# ZYNQ.net
KiCad netlist of a schematic drawn in Altium Designer
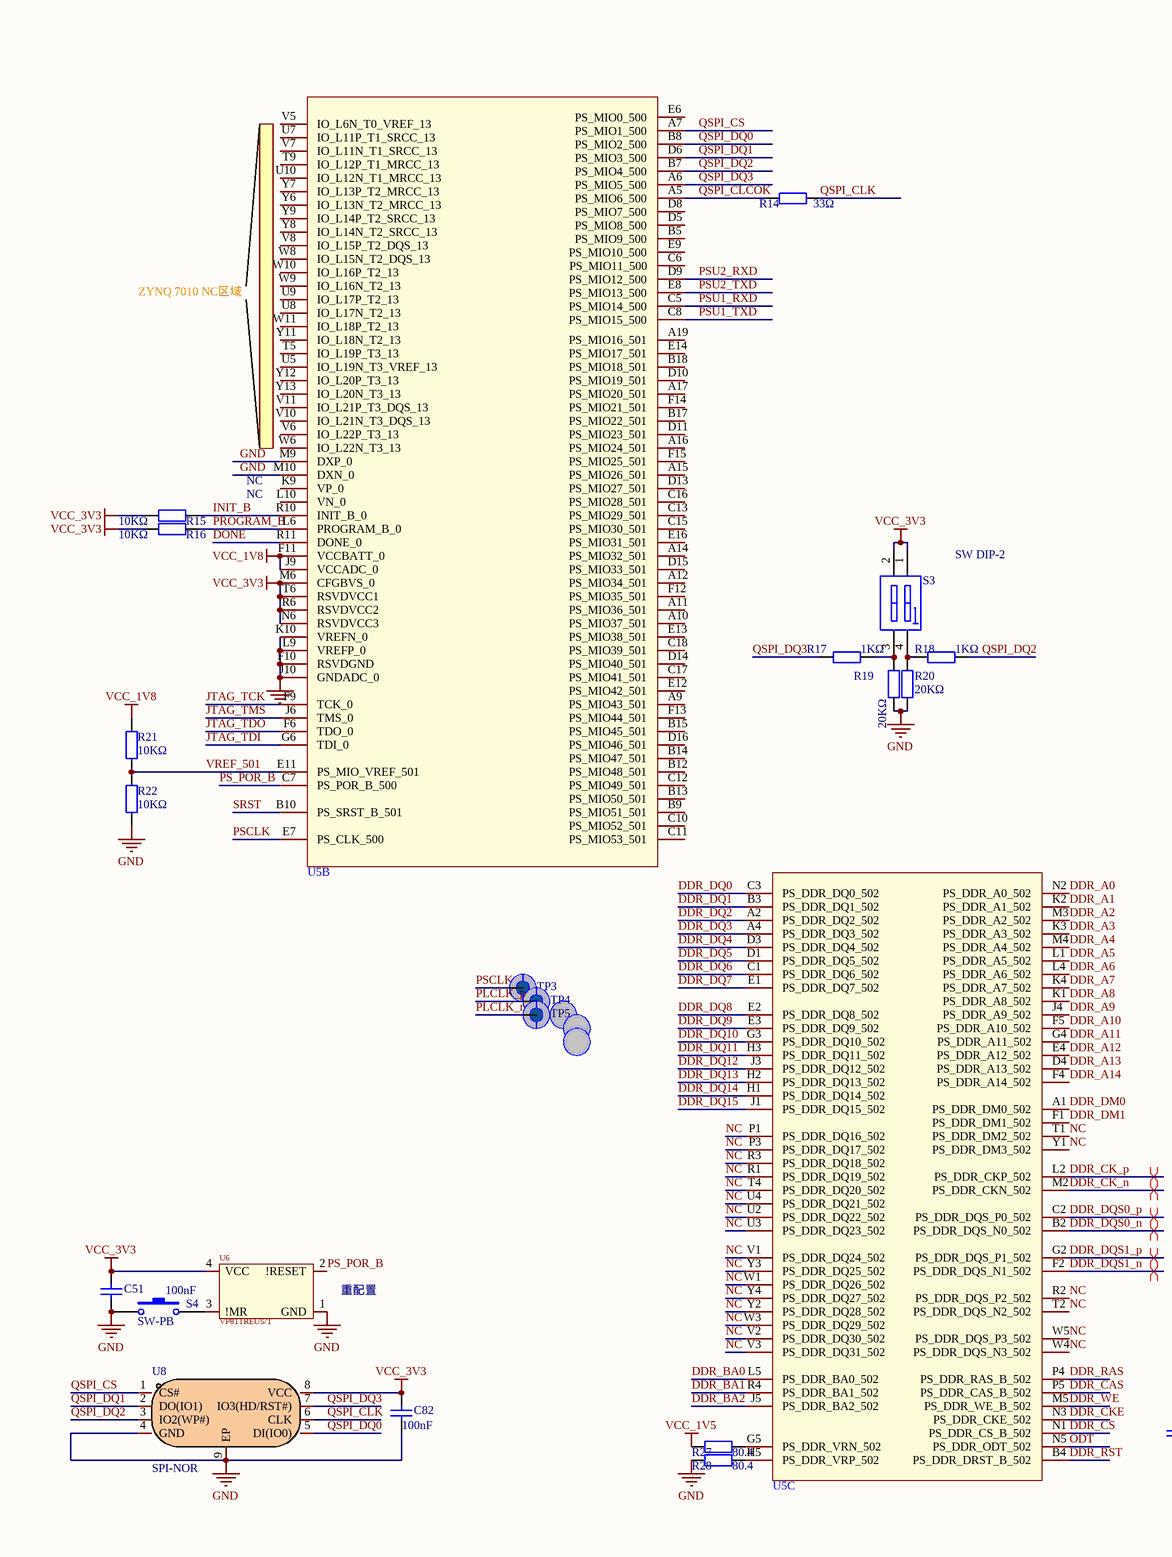
[diagram p0: ZYNQ.SchDoc, left]
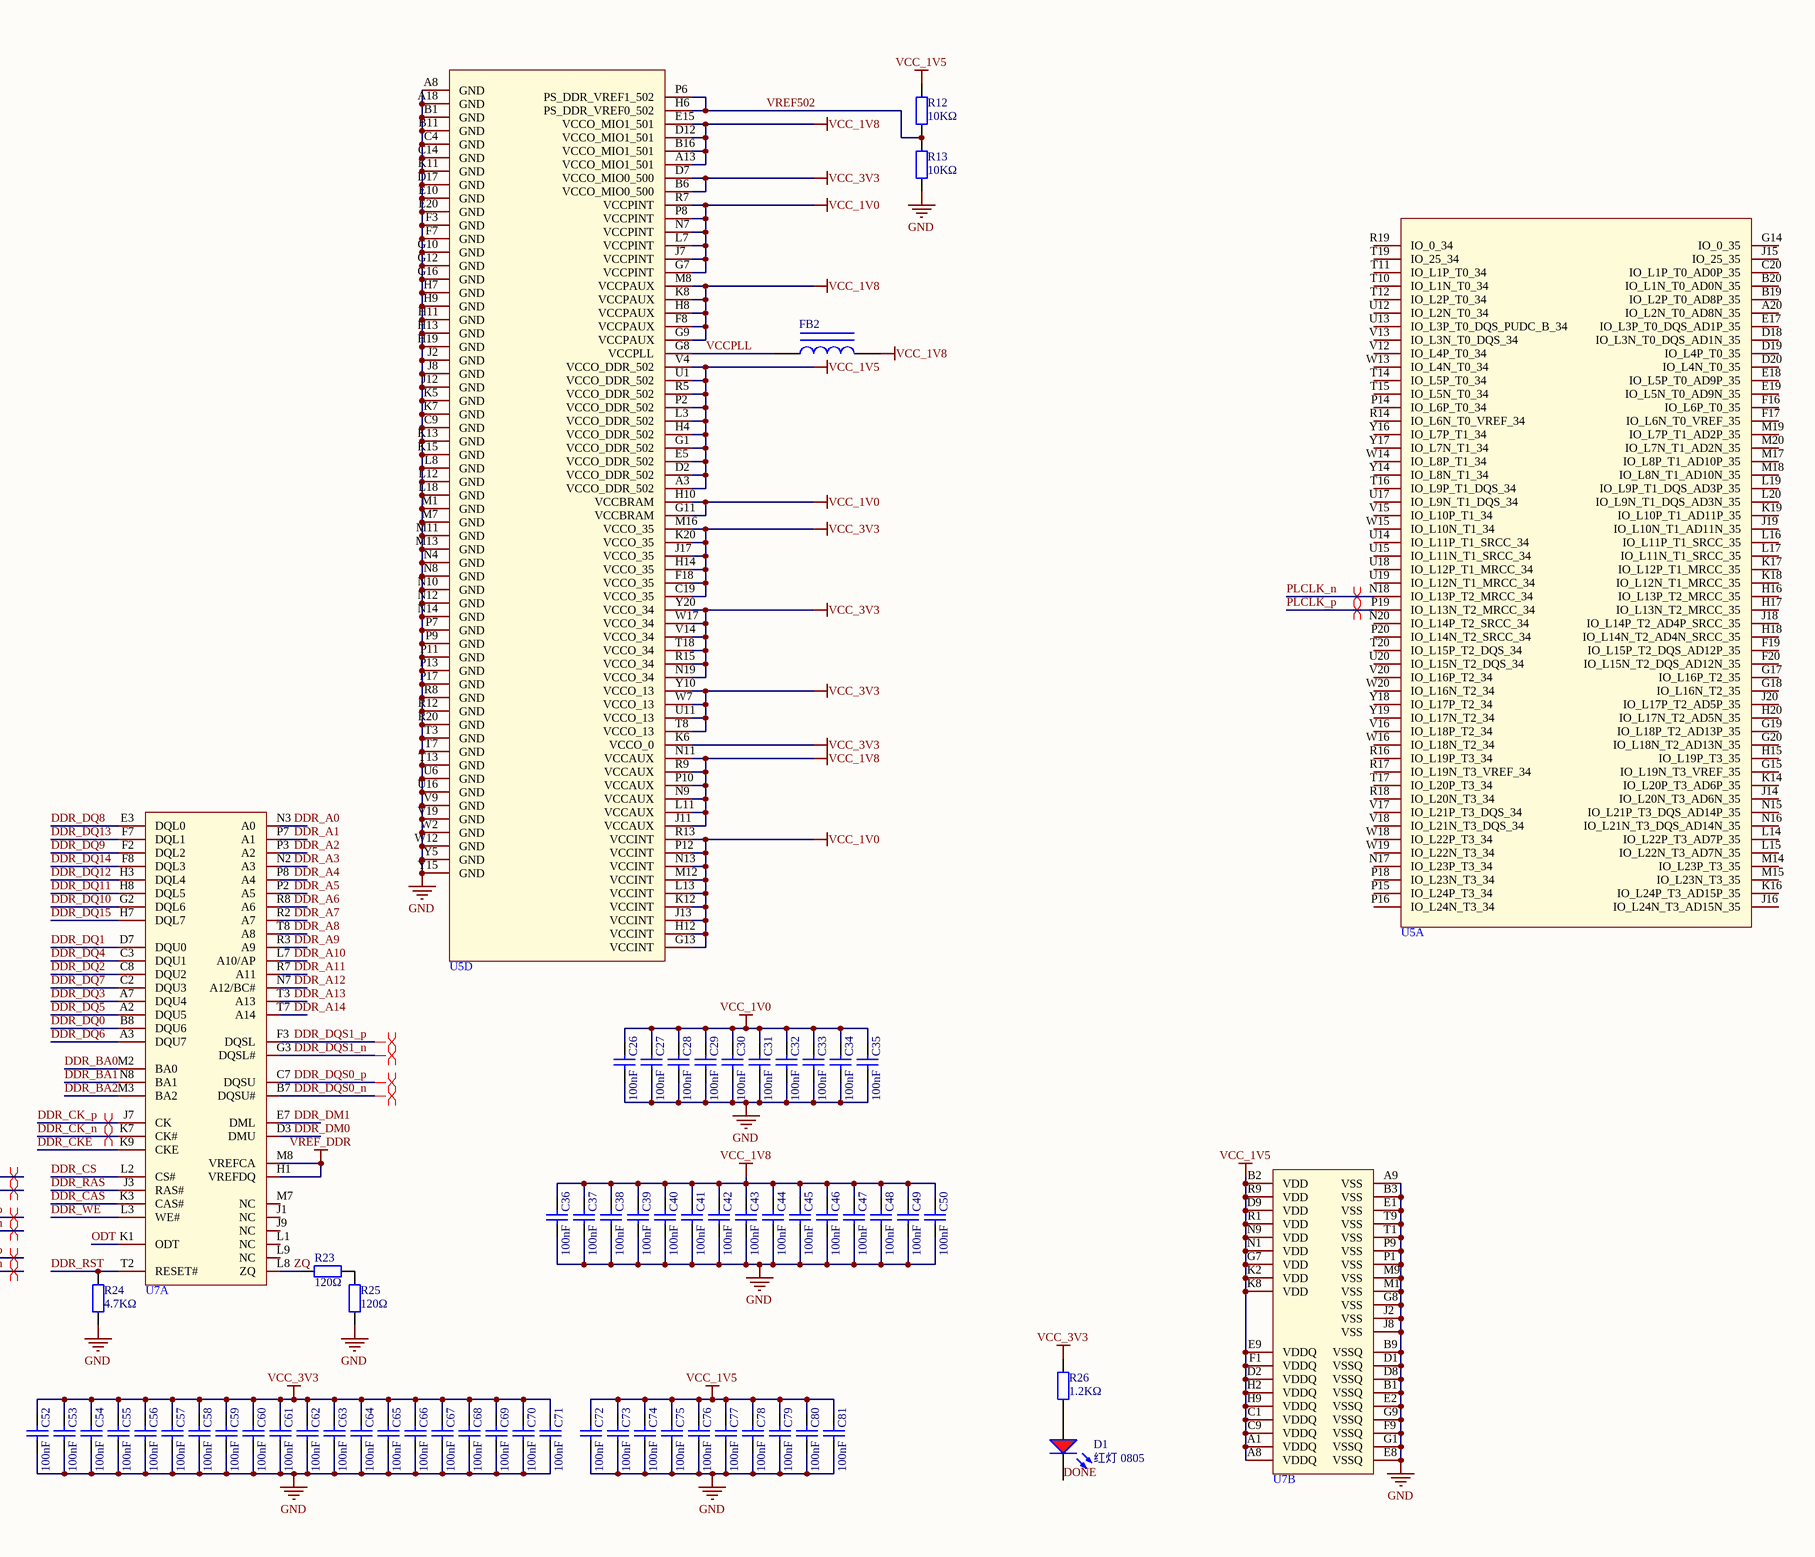
[diagram p1: ZYNQ.SchDoc, right]

(export (version "E")
  (design (tool "Eeschema 10.0.6"))
  (components
    (comp (ref "C26")
      (value "100nF")
      (footprint "0201")
      (description "贴片电容")
      (libsource (lib "Miscellaneous Devices LC") (part "0402 100nF (104) 10% 16V"))
    )
    (comp (ref "C27")
      (value "100nF")
      (footprint "0201")
      (description "贴片电容")
      (libsource (lib "Miscellaneous Devices LC") (part "0402 100nF (104) 10% 16V"))
    )
    (comp (ref "C28")
      (value "100nF")
      (footprint "0201")
      (description "贴片电容")
      (libsource (lib "Miscellaneous Devices LC") (part "0402 100nF (104) 10% 16V"))
    )
    (comp (ref "C29")
      (value "100nF")
      (footprint "0201")
      (description "贴片电容")
      (libsource (lib "Miscellaneous Devices LC") (part "0402 100nF (104) 10% 16V"))
    )
    (comp (ref "C30")
      (value "100nF")
      (footprint "0201")
      (description "贴片电容")
      (libsource (lib "Miscellaneous Devices LC") (part "0402 100nF (104) 10% 16V"))
    )
    (comp (ref "C31")
      (value "100nF")
      (footprint "0201")
      (description "贴片电容")
      (libsource (lib "Miscellaneous Devices LC") (part "0402 100nF (104) 10% 16V"))
    )
    (comp (ref "C32")
      (value "100nF")
      (footprint "0201")
      (description "贴片电容")
      (libsource (lib "Miscellaneous Devices LC") (part "0402 100nF (104) 10% 16V"))
    )
    (comp (ref "C33")
      (value "100nF")
      (footprint "0201")
      (description "贴片电容")
      (libsource (lib "Miscellaneous Devices LC") (part "0402 100nF (104) 10% 16V"))
    )
    (comp (ref "C34")
      (value "100nF")
      (footprint "0201")
      (description "贴片电容")
      (libsource (lib "Miscellaneous Devices LC") (part "0402 100nF (104) 10% 16V"))
    )
    (comp (ref "C35")
      (value "100nF")
      (footprint "0201")
      (description "贴片电容")
      (libsource (lib "Miscellaneous Devices LC") (part "0402 100nF (104) 10% 16V"))
    )
    (comp (ref "C36")
      (value "100nF")
      (footprint "0201")
      (description "贴片电容")
      (libsource (lib "Miscellaneous Devices LC") (part "0402 100nF (104) 10% 16V"))
    )
    (comp (ref "C37")
      (value "100nF")
      (footprint "0201")
      (description "贴片电容")
      (libsource (lib "Miscellaneous Devices LC") (part "0402 100nF (104) 10% 16V"))
    )
    (comp (ref "C38")
      (value "100nF")
      (footprint "0201")
      (description "贴片电容")
      (libsource (lib "Miscellaneous Devices LC") (part "0402 100nF (104) 10% 16V"))
    )
    (comp (ref "C39")
      (value "100nF")
      (footprint "0201")
      (description "贴片电容")
      (libsource (lib "Miscellaneous Devices LC") (part "0402 100nF (104) 10% 16V"))
    )
    (comp (ref "C40")
      (value "100nF")
      (footprint "0201")
      (description "贴片电容")
      (libsource (lib "Miscellaneous Devices LC") (part "0402 100nF (104) 10% 16V"))
    )
    (comp (ref "C41")
      (value "100nF")
      (footprint "0201")
      (description "贴片电容")
      (libsource (lib "Miscellaneous Devices LC") (part "0402 100nF (104) 10% 16V"))
    )
    (comp (ref "C42")
      (value "100nF")
      (footprint "0201")
      (description "贴片电容")
      (libsource (lib "Miscellaneous Devices LC") (part "0402 100nF (104) 10% 16V"))
    )
    (comp (ref "C43")
      (value "100nF")
      (footprint "0201")
      (description "贴片电容")
      (libsource (lib "Miscellaneous Devices LC") (part "0402 100nF (104) 10% 16V"))
    )
    (comp (ref "C44")
      (value "100nF")
      (footprint "0201")
      (description "贴片电容")
      (libsource (lib "Miscellaneous Devices LC") (part "0402 100nF (104) 10% 16V"))
    )
    (comp (ref "C45")
      (value "100nF")
      (footprint "0201")
      (description "贴片电容")
      (libsource (lib "Miscellaneous Devices LC") (part "0402 100nF (104) 10% 16V"))
    )
    (comp (ref "C46")
      (value "100nF")
      (footprint "0201")
      (description "贴片电容")
      (libsource (lib "Miscellaneous Devices LC") (part "0402 100nF (104) 10% 16V"))
    )
    (comp (ref "C47")
      (value "100nF")
      (footprint "0201")
      (description "贴片电容")
      (libsource (lib "Miscellaneous Devices LC") (part "0402 100nF (104) 10% 16V"))
    )
    (comp (ref "C48")
      (value "100nF")
      (footprint "0201")
      (description "贴片电容")
      (libsource (lib "Miscellaneous Devices LC") (part "0402 100nF (104) 10% 16V"))
    )
    (comp (ref "C49")
      (value "100nF")
      (footprint "0201")
      (description "贴片电容")
      (libsource (lib "Miscellaneous Devices LC") (part "0402 100nF (104) 10% 16V"))
    )
    (comp (ref "C50")
      (value "100nF")
      (footprint "0201")
      (description "贴片电容")
      (libsource (lib "Miscellaneous Devices LC") (part "0402 100nF (104) 10% 16V"))
    )
    (comp (ref "C51")
      (value "100nF")
      (footprint "0805_C")
      (description "贴片电容")
      (libsource (lib "Miscellaneous Devices LC") (part "0402 100nF (104) 10% 16V"))
    )
    (comp (ref "C52")
      (value "100nF")
      (footprint "0201")
      (description "贴片电容")
      (libsource (lib "Miscellaneous Devices LC") (part "0402 100nF (104) 10% 16V"))
    )
    (comp (ref "C53")
      (value "100nF")
      (footprint "0201")
      (description "贴片电容")
      (libsource (lib "Miscellaneous Devices LC") (part "0402 100nF (104) 10% 16V"))
    )
    (comp (ref "C54")
      (value "100nF")
      (footprint "0201")
      (description "贴片电容")
      (libsource (lib "Miscellaneous Devices LC") (part "0402 100nF (104) 10% 16V"))
    )
    (comp (ref "C55")
      (value "100nF")
      (footprint "0201")
      (description "贴片电容")
      (libsource (lib "Miscellaneous Devices LC") (part "0402 100nF (104) 10% 16V"))
    )
    (comp (ref "C56")
      (value "100nF")
      (footprint "0201")
      (description "贴片电容")
      (libsource (lib "Miscellaneous Devices LC") (part "0402 100nF (104) 10% 16V"))
    )
    (comp (ref "C57")
      (value "100nF")
      (footprint "0201")
      (description "贴片电容")
      (libsource (lib "Miscellaneous Devices LC") (part "0402 100nF (104) 10% 16V"))
    )
    (comp (ref "C58")
      (value "100nF")
      (footprint "0201")
      (description "贴片电容")
      (libsource (lib "Miscellaneous Devices LC") (part "0402 100nF (104) 10% 16V"))
    )
    (comp (ref "C59")
      (value "100nF")
      (footprint "0201")
      (description "贴片电容")
      (libsource (lib "Miscellaneous Devices LC") (part "0402 100nF (104) 10% 16V"))
    )
    (comp (ref "C60")
      (value "100nF")
      (footprint "0201")
      (description "贴片电容")
      (libsource (lib "Miscellaneous Devices LC") (part "0402 100nF (104) 10% 16V"))
    )
    (comp (ref "C61")
      (value "100nF")
      (footprint "0201")
      (description "贴片电容")
      (libsource (lib "Miscellaneous Devices LC") (part "0402 100nF (104) 10% 16V"))
    )
    (comp (ref "C62")
      (value "100nF")
      (footprint "0201")
      (description "贴片电容")
      (libsource (lib "Miscellaneous Devices LC") (part "0402 100nF (104) 10% 16V"))
    )
    (comp (ref "C63")
      (value "100nF")
      (footprint "0201")
      (description "贴片电容")
      (libsource (lib "Miscellaneous Devices LC") (part "0402 100nF (104) 10% 16V"))
    )
    (comp (ref "C64")
      (value "100nF")
      (footprint "0201")
      (description "贴片电容")
      (libsource (lib "Miscellaneous Devices LC") (part "0402 100nF (104) 10% 16V"))
    )
    (comp (ref "C65")
      (value "100nF")
      (footprint "0201")
      (description "贴片电容")
      (libsource (lib "Miscellaneous Devices LC") (part "0402 100nF (104) 10% 16V"))
    )
    (comp (ref "C66")
      (value "100nF")
      (footprint "0201")
      (description "贴片电容")
      (libsource (lib "Miscellaneous Devices LC") (part "0402 100nF (104) 10% 16V"))
    )
    (comp (ref "C67")
      (value "100nF")
      (footprint "0201")
      (description "贴片电容")
      (libsource (lib "Miscellaneous Devices LC") (part "0402 100nF (104) 10% 16V"))
    )
    (comp (ref "C68")
      (value "100nF")
      (footprint "0201")
      (description "贴片电容")
      (libsource (lib "Miscellaneous Devices LC") (part "0402 100nF (104) 10% 16V"))
    )
    (comp (ref "C69")
      (value "100nF")
      (footprint "0201")
      (description "贴片电容")
      (libsource (lib "Miscellaneous Devices LC") (part "0402 100nF (104) 10% 16V"))
    )
    (comp (ref "C70")
      (value "100nF")
      (footprint "0201")
      (description "贴片电容")
      (libsource (lib "Miscellaneous Devices LC") (part "0402 100nF (104) 10% 16V"))
    )
    (comp (ref "C71")
      (value "100nF")
      (footprint "0201")
      (description "贴片电容")
      (libsource (lib "Miscellaneous Devices LC") (part "0402 100nF (104) 10% 16V"))
    )
    (comp (ref "C72")
      (value "100nF")
      (footprint "0201")
      (description "贴片电容")
      (libsource (lib "Miscellaneous Devices LC") (part "0402 100nF (104) 10% 16V"))
    )
    (comp (ref "C73")
      (value "100nF")
      (footprint "0201")
      (description "贴片电容")
      (libsource (lib "Miscellaneous Devices LC") (part "0402 100nF (104) 10% 16V"))
    )
    (comp (ref "C74")
      (value "100nF")
      (footprint "0201")
      (description "贴片电容")
      (libsource (lib "Miscellaneous Devices LC") (part "0402 100nF (104) 10% 16V"))
    )
    (comp (ref "C75")
      (value "100nF")
      (footprint "0201")
      (description "贴片电容")
      (libsource (lib "Miscellaneous Devices LC") (part "0402 100nF (104) 10% 16V"))
    )
    (comp (ref "C76")
      (value "100nF")
      (footprint "0201")
      (description "贴片电容")
      (libsource (lib "Miscellaneous Devices LC") (part "0402 100nF (104) 10% 16V"))
    )
    (comp (ref "C77")
      (value "100nF")
      (footprint "0201")
      (description "贴片电容")
      (libsource (lib "Miscellaneous Devices LC") (part "0402 100nF (104) 10% 16V"))
    )
    (comp (ref "C78")
      (value "100nF")
      (footprint "0201")
      (description "贴片电容")
      (libsource (lib "Miscellaneous Devices LC") (part "0402 100nF (104) 10% 16V"))
    )
    (comp (ref "C79")
      (value "100nF")
      (footprint "0201")
      (description "贴片电容")
      (libsource (lib "Miscellaneous Devices LC") (part "0402 100nF (104) 10% 16V"))
    )
    (comp (ref "C80")
      (value "100nF")
      (footprint "0201")
      (description "贴片电容")
      (libsource (lib "Miscellaneous Devices LC") (part "0402 100nF (104) 10% 16V"))
    )
    (comp (ref "C81")
      (value "100nF")
      (footprint "0201")
      (description "贴片电容")
      (libsource (lib "Miscellaneous Devices LC") (part "0402 100nF (104) 10% 16V"))
    )
    (comp (ref "C82")
      (value "100nF")
      (footprint "0805_C")
      (description "贴片电容")
      (libsource (lib "Miscellaneous Devices LC") (part "0402 100nF (104) 10% 16V"))
    )
    (comp (ref "D1")
      (value "红灯 0805")
      (footprint "0805_LED_S1")
      (description "发光二极管")
      (libsource (lib "Miscellaneous Devices LC") (part "0805 红灯"))
    )
    (comp (ref "FB2")
      (value "100Ω ±25% 100MHz")
      (footprint "0805_L")
      (description "贴片磁珠")
      (libsource (lib "Miscellaneous Devices LC") (part "0805 100Ω 25% 100MHz"))
    )
    (comp (ref "R12")
      (value "10KΩ")
      (footprint "0201")
      (description "贴片电阻")
      (libsource (lib "Miscellaneous Devices LC") (part "0805 10KΩ (1002) 1%"))
    )
    (comp (ref "R13")
      (value "10KΩ")
      (footprint "0201")
      (description "贴片电阻")
      (libsource (lib "Miscellaneous Devices LC") (part "0805 10KΩ (1002) 1%"))
    )
    (comp (ref "R14")
      (value "33Ω")
      (footprint "0805_R")
      (description "贴片电阻")
      (libsource (lib "Miscellaneous Devices LC") (part "0402 33Ω (33R0) 1%"))
    )
    (comp (ref "R15")
      (value "10KΩ")
      (footprint "0201")
      (description "贴片电阻")
      (libsource (lib "Miscellaneous Devices LC") (part "0402 4.7KΩ (4701) 1%"))
    )
    (comp (ref "R16")
      (value "10KΩ")
      (footprint "0201")
      (description "贴片电阻")
      (libsource (lib "Miscellaneous Devices LC") (part "0402 4.7KΩ (4701) 1%"))
    )
    (comp (ref "R17")
      (value "1KΩ")
      (footprint "0805_R")
      (description "贴片电阻")
      (libsource (lib "Miscellaneous Devices LC") (part "0402 10KΩ (1002) 1%"))
    )
    (comp (ref "R18")
      (value "1KΩ")
      (footprint "0805_R")
      (description "贴片电阻")
      (libsource (lib "Miscellaneous Devices LC") (part "0402 10KΩ (1002) 1%"))
    )
    (comp (ref "R19")
      (value "20KΩ")
      (footprint "0805_R")
      (description "贴片电阻")
      (libsource (lib "Miscellaneous Devices LC") (part "0402 20KΩ (2002) 1%"))
    )
    (comp (ref "R20")
      (value "20KΩ")
      (footprint "0805_R")
      (description "贴片电阻")
      (libsource (lib "Miscellaneous Devices LC") (part "0402 20KΩ (2002) 1%"))
    )
    (comp (ref "R21")
      (value "10KΩ")
      (footprint "0201")
      (description "贴片电阻")
      (libsource (lib "Miscellaneous Devices LC") (part "0805 10KΩ (1002) 1%"))
    )
    (comp (ref "R22")
      (value "10KΩ")
      (footprint "0201")
      (description "贴片电阻")
      (libsource (lib "Miscellaneous Devices LC") (part "0805 10KΩ (1002) 1%"))
    )
    (comp (ref "R23")
      (value "120Ω")
      (footprint "0805_R")
      (description "贴片电阻")
      (libsource (lib "Miscellaneous Devices LC") (part "0402 120Ω (1200) 1%"))
    )
    (comp (ref "R24")
      (value "4.7KΩ")
      (footprint "0805_R")
      (description "贴片电阻")
      (libsource (lib "") (part "0402 4.7KΩ (4701) 1%_1"))
    )
    (comp (ref "R25")
      (value "120Ω")
      (footprint "0805_R")
      (description "贴片电阻")
      (libsource (lib "") (part "0402 120Ω (1200) 1%_1"))
    )
    (comp (ref "R26")
      (value "1.2KΩ")
      (footprint "0805_R")
      (description "贴片电阻")
      (libsource (lib "Miscellaneous Devices LC") (part "0805 1.2KΩ (1201) 1%"))
    )
    (comp (ref "R27")
      (value "80.4")
      (footprint "0402_R")
      (description "贴片电阻")
      (libsource (lib "Miscellaneous Devices LC") (part "0402 0Ω (0R0) 1%"))
    )
    (comp (ref "R28")
      (value "80.4")
      (footprint "0402_R")
      (description "贴片电阻")
      (libsource (lib "Miscellaneous Devices LC") (part "0402 0Ω (0R0) 1%"))
    )
    (comp (ref "S3")
      (value "SW DIP-2")
      (footprint "SW-SMD_DSHP02TS-S")
      (description "DIP Switch, 2 Position, SPST")
      (fields (field (name "PUBLISHER") "Altium Limited"))
      (libsource (lib "Miscellaneous Devices") (part "SW DIP-2"))
    )
    (comp (ref "S4")
      (value "SW-PB")
      (footprint "SW-3*4-2P")
      (description "Switch")
      (fields (field (name "PUBLISHER") "Altium Limited"))
      (libsource (lib "Miscellaneous Devices") (part "SW-PB"))
    )
    (comp (ref "TP3")
      (value "test-point")
      (footprint "POINT")
      (description "测试点")
      (libsource (lib "五向开关") (part "test-point"))
    )
    (comp (ref "TP4")
      (value "test-point")
      (footprint "POINT")
      (description "测试点")
      (libsource (lib "五向开关") (part "test-point"))
    )
    (comp (ref "TP5")
      (value "test-point")
      (footprint "POINT")
      (description "测试点")
      (libsource (lib "五向开关") (part "test-point"))
    )
    (comp (ref "U5")
      (value "XC7Z020-2CLG400I")
      (footprint "FBGA-400_L17.0-W17.0-R20-C20-P0.80-TL")
      (fields (field (name "MANUFACTURER") "XILINX(赛灵思)"))
      (libsource (lib "五向开关") (part "XC7Z020-2CLG400I"))
    )
    (comp (ref "U6")
      (value "VP811REUS/T")
      (footprint "SOT-143_L2.9-W1.3-P1.92-LS2.3-BL")
      (description "复位电平管理芯片")
      (fields (field (name "MANUFACTURER") "VP(中芯集成)"))
      (libsource (lib "五向开关") (part "VP811REUS/T"))
    )
    (comp (ref "U7")
      (value "NT5CC256M16ER-EK")
      (footprint "TFBGA-96_L13.0-W8.0-R16-C6-P0.80-TL")
      (fields (field (name "MANUFACTURER") "Nanya(南亚科技)"))
      (libsource (lib "五向开关") (part "4Gbit DDR3L BGA-96"))
    )
    (comp (ref "U8")
      (value "SPI-NOR")
      (footprint "WSON8")
      (description "NOR FLASH")
      (libsource (lib "五向开关") (part "W25Q64"))
    )
  )
  (nets
    (net (code "1") (name "/DDR_A0") (class "Default")
      (node (ref "U5") (pin "N2") (pinfunction "PS_DDR_A0_502_N2") (pintype "passive"))
      (node (ref "U7") (pin "N3") (pinfunction "A0_N3") (pintype "passive"))
    )
    (net (code "2") (name "/DDR_A1") (class "Default")
      (node (ref "U5") (pin "K2") (pinfunction "PS_DDR_A1_502_K2") (pintype "passive"))
      (node (ref "U7") (pin "P7") (pinfunction "A1_P7") (pintype "passive"))
    )
    (net (code "3") (name "/DDR_A2") (class "Default")
      (node (ref "U5") (pin "M3") (pinfunction "PS_DDR_A2_502_M3") (pintype "passive"))
      (node (ref "U7") (pin "P3") (pinfunction "A2_P3") (pintype "passive"))
    )
    (net (code "4") (name "/DDR_A3") (class "Default")
      (node (ref "U5") (pin "K3") (pinfunction "PS_DDR_A3_502_K3") (pintype "passive"))
      (node (ref "U7") (pin "N2") (pinfunction "A3_N2") (pintype "passive"))
    )
    (net (code "5") (name "/DDR_A4") (class "Default")
      (node (ref "U5") (pin "M4") (pinfunction "PS_DDR_A4_502_M4") (pintype "passive"))
      (node (ref "U7") (pin "P8") (pinfunction "A4_P8") (pintype "passive"))
    )
    (net (code "6") (name "/DDR_A5") (class "Default")
      (node (ref "U5") (pin "L1") (pinfunction "PS_DDR_A5_502_L1") (pintype "passive"))
      (node (ref "U7") (pin "P2") (pinfunction "A5_P2") (pintype "passive"))
    )
    (net (code "7") (name "/DDR_A6") (class "Default")
      (node (ref "U5") (pin "L4") (pinfunction "PS_DDR_A6_502_L4") (pintype "passive"))
      (node (ref "U7") (pin "R8") (pinfunction "A6_R8") (pintype "passive"))
    )
    (net (code "8") (name "/DDR_A7") (class "Default")
      (node (ref "U5") (pin "K4") (pinfunction "PS_DDR_A7_502_K4") (pintype "passive"))
      (node (ref "U7") (pin "R2") (pinfunction "A7_R2") (pintype "passive"))
    )
    (net (code "9") (name "/DDR_A8") (class "Default")
      (node (ref "U5") (pin "K1") (pinfunction "PS_DDR_A8_502_K1") (pintype "passive"))
      (node (ref "U7") (pin "T8") (pinfunction "A8_T8") (pintype "passive"))
    )
    (net (code "10") (name "/DDR_A9") (class "Default")
      (node (ref "U5") (pin "J4") (pinfunction "PS_DDR_A9_502_J4") (pintype "passive"))
      (node (ref "U7") (pin "R3") (pinfunction "A9_R3") (pintype "passive"))
    )
    (net (code "11") (name "/DDR_A10") (class "Default")
      (node (ref "U5") (pin "F5") (pinfunction "PS_DDR_A10_502_F5") (pintype "passive"))
      (node (ref "U7") (pin "L7") (pinfunction "A10/AP_L7") (pintype "passive"))
    )
    (net (code "12") (name "/DDR_A11") (class "Default")
      (node (ref "U5") (pin "G4") (pinfunction "PS_DDR_A11_502_G4") (pintype "passive"))
      (node (ref "U7") (pin "R7") (pinfunction "A11_R7") (pintype "passive"))
    )
    (net (code "13") (name "/DDR_A12") (class "Default")
      (node (ref "U5") (pin "E4") (pinfunction "PS_DDR_A12_502_E4") (pintype "passive"))
      (node (ref "U7") (pin "N7") (pinfunction "A12/BC#_N7") (pintype "passive"))
    )
    (net (code "14") (name "/DDR_A13") (class "Default")
      (node (ref "U5") (pin "D4") (pinfunction "PS_DDR_A13_502_D4") (pintype "passive"))
      (node (ref "U7") (pin "T3") (pinfunction "A13_T3") (pintype "passive"))
    )
    (net (code "15") (name "/DDR_A14") (class "Default")
      (node (ref "U5") (pin "F4") (pinfunction "PS_DDR_A14_502_F4") (pintype "passive"))
      (node (ref "U7") (pin "T7") (pinfunction "A14_T7") (pintype "passive"))
    )
    (net (code "16") (name "/DDR_BA0") (class "Default")
      (node (ref "U5") (pin "L5") (pinfunction "PS_DDR_BA0_502_L5") (pintype "passive"))
      (node (ref "U7") (pin "M2") (pinfunction "BA0_M2") (pintype "passive"))
    )
    (net (code "17") (name "/DDR_BA1") (class "Default")
      (node (ref "U5") (pin "R4") (pinfunction "PS_DDR_BA1_502_R4") (pintype "passive"))
      (node (ref "U7") (pin "N8") (pinfunction "BA1_N8") (pintype "passive"))
    )
    (net (code "18") (name "/DDR_BA2") (class "Default")
      (node (ref "U5") (pin "J5") (pinfunction "PS_DDR_BA2_502_J5") (pintype "passive"))
      (node (ref "U7") (pin "M3") (pinfunction "BA2_M3") (pintype "passive"))
    )
    (net (code "19") (name "/DDR_CAS") (class "Default")
      (node (ref "U5") (pin "P5") (pinfunction "PS_DDR_CAS_B_502_P5") (pintype "passive"))
      (node (ref "U7") (pin "K3") (pinfunction "CAS#_K3") (pintype "passive"))
    )
    (net (code "20") (name "/DDR_CKE") (class "Default")
      (node (ref "U5") (pin "N3") (pinfunction "PS_DDR_CKE_502_N3") (pintype "passive"))
      (node (ref "U7") (pin "K9") (pinfunction "CKE_K9") (pintype "passive"))
    )
    (net (code "21") (name "/DDR_CK_n") (class "Default")
      (node (ref "U5") (pin "M2") (pinfunction "PS_DDR_CKN_502_M2") (pintype "passive"))
      (node (ref "U7") (pin "K7") (pinfunction "CK#_K7") (pintype "passive"))
    )
    (net (code "22") (name "/DDR_CK_p") (class "Default")
      (node (ref "U5") (pin "L2") (pinfunction "PS_DDR_CKP_502_L2") (pintype "passive"))
      (node (ref "U7") (pin "J7") (pinfunction "CK_J7") (pintype "passive"))
    )
    (net (code "23") (name "/DDR_CS") (class "Default")
      (node (ref "U5") (pin "N1") (pinfunction "PS_DDR_CS_B_502_N1") (pintype "passive"))
      (node (ref "U7") (pin "L2") (pinfunction "CS#_L2") (pintype "passive"))
    )
    (net (code "24") (name "/DDR_DM0") (class "Default")
      (node (ref "U5") (pin "A1") (pinfunction "PS_DDR_DM0_502_A1") (pintype "passive"))
      (node (ref "U7") (pin "D3") (pinfunction "DMU_D3") (pintype "passive"))
    )
    (net (code "25") (name "/DDR_DM1") (class "Default")
      (node (ref "U5") (pin "F1") (pinfunction "PS_DDR_DM1_502_F1") (pintype "passive"))
      (node (ref "U7") (pin "E7") (pinfunction "DML_E7") (pintype "passive"))
    )
    (net (code "26") (name "/DDR_DQ0") (class "Default")
      (node (ref "U5") (pin "C3") (pinfunction "PS_DDR_DQ0_502_C3") (pintype "passive"))
      (node (ref "U7") (pin "B8") (pinfunction "DQU6_B8") (pintype "passive"))
    )
    (net (code "27") (name "/DDR_DQ1") (class "Default")
      (node (ref "U5") (pin "B3") (pinfunction "PS_DDR_DQ1_502_B3") (pintype "passive"))
      (node (ref "U7") (pin "D7") (pinfunction "DQU0_D7") (pintype "passive"))
    )
    (net (code "28") (name "/DDR_DQ2") (class "Default")
      (node (ref "U5") (pin "A2") (pinfunction "PS_DDR_DQ2_502_A2") (pintype "passive"))
      (node (ref "U7") (pin "C8") (pinfunction "DQU2_C8") (pintype "passive"))
    )
    (net (code "29") (name "/DDR_DQ3") (class "Default")
      (node (ref "U5") (pin "A4") (pinfunction "PS_DDR_DQ3_502_A4") (pintype "passive"))
      (node (ref "U7") (pin "A7") (pinfunction "DQU4_A7") (pintype "passive"))
    )
    (net (code "30") (name "/DDR_DQ4") (class "Default")
      (node (ref "U5") (pin "D3") (pinfunction "PS_DDR_DQ4_502_D3") (pintype "passive"))
      (node (ref "U7") (pin "C3") (pinfunction "DQU1_C3") (pintype "passive"))
    )
    (net (code "31") (name "/DDR_DQ5") (class "Default")
      (node (ref "U5") (pin "D1") (pinfunction "PS_DDR_DQ5_502_D1") (pintype "passive"))
      (node (ref "U7") (pin "A2") (pinfunction "DQU5_A2") (pintype "passive"))
    )
    (net (code "32") (name "/DDR_DQ6") (class "Default")
      (node (ref "U5") (pin "C1") (pinfunction "PS_DDR_DQ6_502_C1") (pintype "passive"))
      (node (ref "U7") (pin "A3") (pinfunction "DQU7_A3") (pintype "passive"))
    )
    (net (code "33") (name "/DDR_DQ7") (class "Default")
      (node (ref "U5") (pin "E1") (pinfunction "PS_DDR_DQ7_502_E1") (pintype "passive"))
      (node (ref "U7") (pin "C2") (pinfunction "DQU3_C2") (pintype "passive"))
    )
    (net (code "34") (name "/DDR_DQ8") (class "Default")
      (node (ref "U5") (pin "E2") (pinfunction "PS_DDR_DQ8_502_E2") (pintype "passive"))
      (node (ref "U7") (pin "E3") (pinfunction "DQL0_E3") (pintype "passive"))
    )
    (net (code "35") (name "/DDR_DQ9") (class "Default")
      (node (ref "U5") (pin "E3") (pinfunction "PS_DDR_DQ9_502_E3") (pintype "passive"))
      (node (ref "U7") (pin "F2") (pinfunction "DQL2_F2") (pintype "passive"))
    )
    (net (code "36") (name "/DDR_DQ10") (class "Default")
      (node (ref "U5") (pin "G3") (pinfunction "PS_DDR_DQ10_502_G3") (pintype "passive"))
      (node (ref "U7") (pin "G2") (pinfunction "DQL6_G2") (pintype "passive"))
    )
    (net (code "37") (name "/DDR_DQ11") (class "Default")
      (node (ref "U5") (pin "H3") (pinfunction "PS_DDR_DQ11_502_H3") (pintype "passive"))
      (node (ref "U7") (pin "H8") (pinfunction "DQL5_H8") (pintype "passive"))
    )
    (net (code "38") (name "/DDR_DQ12") (class "Default")
      (node (ref "U5") (pin "J3") (pinfunction "PS_DDR_DQ12_502_J3") (pintype "passive"))
      (node (ref "U7") (pin "H3") (pinfunction "DQL4_H3") (pintype "passive"))
    )
    (net (code "39") (name "/DDR_DQ13") (class "Default")
      (node (ref "U5") (pin "H2") (pinfunction "PS_DDR_DQ13_502_H2") (pintype "passive"))
      (node (ref "U7") (pin "F7") (pinfunction "DQL1_F7") (pintype "passive"))
    )
    (net (code "40") (name "/DDR_DQ14") (class "Default")
      (node (ref "U5") (pin "H1") (pinfunction "PS_DDR_DQ14_502_H1") (pintype "passive"))
      (node (ref "U7") (pin "F8") (pinfunction "DQL3_F8") (pintype "passive"))
    )
    (net (code "41") (name "/DDR_DQ15") (class "Default")
      (node (ref "U5") (pin "J1") (pinfunction "PS_DDR_DQ15_502_J1") (pintype "passive"))
      (node (ref "U7") (pin "H7") (pinfunction "DQL7_H7") (pintype "passive"))
    )
    (net (code "42") (name "/DDR_DQS0_n") (class "Default")
      (node (ref "U5") (pin "B2") (pinfunction "PS_DDR_DQS_N0_502_B2") (pintype "passive"))
      (node (ref "U7") (pin "B7") (pinfunction "DQSU#_B7") (pintype "passive"))
    )
    (net (code "43") (name "/DDR_DQS0_p") (class "Default")
      (node (ref "U5") (pin "C2") (pinfunction "PS_DDR_DQS_P0_502_C2") (pintype "passive"))
      (node (ref "U7") (pin "C7") (pinfunction "DQSU_C7") (pintype "passive"))
    )
    (net (code "44") (name "/DDR_DQS1_n") (class "Default")
      (node (ref "U5") (pin "F2") (pinfunction "PS_DDR_DQS_N1_502_F2") (pintype "passive"))
      (node (ref "U7") (pin "G3") (pinfunction "DQSL#_G3") (pintype "passive"))
    )
    (net (code "45") (name "/DDR_DQS1_p") (class "Default")
      (node (ref "U5") (pin "G2") (pinfunction "PS_DDR_DQS_P1_502_G2") (pintype "passive"))
      (node (ref "U7") (pin "F3") (pinfunction "DQSL_F3") (pintype "passive"))
    )
    (net (code "46") (name "/DDR_RAS") (class "Default")
      (node (ref "U5") (pin "P4") (pinfunction "PS_DDR_RAS_B_502_P4") (pintype "passive"))
      (node (ref "U7") (pin "J3") (pinfunction "RAS#_J3") (pintype "passive"))
    )
    (net (code "47") (name "/DDR_RST") (class "Default")
      (node (ref "R24") (pin "2") (pinfunction "2_2") (pintype "passive"))
      (node (ref "U5") (pin "B4") (pinfunction "PS_DDR_DRST_B_502_B4") (pintype "passive"))
      (node (ref "U7") (pin "T2") (pinfunction "RESET#_T2") (pintype "passive"))
    )
    (net (code "48") (name "/DDR_WE") (class "Default")
      (node (ref "U5") (pin "M5") (pinfunction "PS_DDR_WE_B_502_M5") (pintype "passive"))
      (node (ref "U7") (pin "L3") (pinfunction "WE#_L3") (pintype "passive"))
    )
    (net (code "49") (name "/DONE") (class "Default")
      (node (ref "D1") (pin "K") (pinfunction "K_K") (pintype "passive"))
      (node (ref "U5") (pin "R11") (pinfunction "DONE_0_R11") (pintype "passive"))
    )
    (net (code "50") (name "/INIT_B") (class "Default")
      (node (ref "R15") (pin "2") (pinfunction "2_2") (pintype "passive"))
      (node (ref "U5") (pin "R10") (pinfunction "INIT_B_0_R10") (pintype "passive"))
    )
    (net (code "51") (name "/JTAG_TCK") (class "Default")
      (node (ref "U5") (pin "F9") (pinfunction "TCK_0_F9") (pintype "passive"))
    )
    (net (code "52") (name "/JTAG_TDI") (class "Default")
      (node (ref "U5") (pin "G6") (pinfunction "TDI_0_G6") (pintype "passive"))
    )
    (net (code "53") (name "/JTAG_TDO") (class "Default")
      (node (ref "U5") (pin "F6") (pinfunction "TDO_0_F6") (pintype "passive"))
    )
    (net (code "54") (name "/JTAG_TMS") (class "Default")
      (node (ref "U5") (pin "J6") (pinfunction "TMS_0_J6") (pintype "passive"))
    )
    (net (code "55") (name "/NC") (class "Default")
      (node (ref "U5") (pin "P1") (pinfunction "PS_DDR_DQ16_502_P1") (pintype "passive"))
      (node (ref "U5") (pin "P3") (pinfunction "PS_DDR_DQ17_502_P3") (pintype "passive"))
      (node (ref "U5") (pin "R1") (pinfunction "PS_DDR_DQ19_502_R1") (pintype "passive"))
      (node (ref "U5") (pin "R2") (pinfunction "PS_DDR_DQS_P2_502_R2") (pintype "passive"))
      (node (ref "U5") (pin "R3") (pinfunction "PS_DDR_DQ18_502_R3") (pintype "passive"))
      (node (ref "U5") (pin "T1") (pinfunction "PS_DDR_DM2_502_T1") (pintype "passive"))
      (node (ref "U5") (pin "T2") (pinfunction "PS_DDR_DQS_N2_502_T2") (pintype "passive"))
      (node (ref "U5") (pin "T4") (pinfunction "PS_DDR_DQ20_502_T4") (pintype "passive"))
      (node (ref "U5") (pin "U2") (pinfunction "PS_DDR_DQ22_502_U2") (pintype "passive"))
      (node (ref "U5") (pin "U3") (pinfunction "PS_DDR_DQ23_502_U3") (pintype "passive"))
      (node (ref "U5") (pin "U4") (pinfunction "PS_DDR_DQ21_502_U4") (pintype "passive"))
      (node (ref "U5") (pin "V1") (pinfunction "PS_DDR_DQ24_502_V1") (pintype "passive"))
      (node (ref "U5") (pin "V2") (pinfunction "PS_DDR_DQ30_502_V2") (pintype "passive"))
      (node (ref "U5") (pin "V3") (pinfunction "PS_DDR_DQ31_502_V3") (pintype "passive"))
      (node (ref "U5") (pin "W1") (pinfunction "PS_DDR_DQ26_502_W1") (pintype "passive"))
      (node (ref "U5") (pin "W3") (pinfunction "PS_DDR_DQ29_502_W3") (pintype "passive"))
      (node (ref "U5") (pin "W4") (pinfunction "PS_DDR_DQS_N3_502_W4") (pintype "passive"))
      (node (ref "U5") (pin "W5") (pinfunction "PS_DDR_DQS_P3_502_W5") (pintype "passive"))
      (node (ref "U5") (pin "Y1") (pinfunction "PS_DDR_DM3_502_Y1") (pintype "passive"))
      (node (ref "U5") (pin "Y2") (pinfunction "PS_DDR_DQ28_502_Y2") (pintype "passive"))
      (node (ref "U5") (pin "Y3") (pinfunction "PS_DDR_DQ25_502_Y3") (pintype "passive"))
      (node (ref "U5") (pin "Y4") (pinfunction "PS_DDR_DQ27_502_Y4") (pintype "passive"))
    )
    (net (code "56") (name "/ODT") (class "Default")
      (node (ref "U5") (pin "N5") (pinfunction "PS_DDR_ODT_502_N5") (pintype "passive"))
      (node (ref "U7") (pin "K1") (pinfunction "ODT_K1") (pintype "passive"))
    )
    (net (code "57") (name "/PLCLK_n") (class "Default")
      (node (ref "TP5") (pin "1") (pinfunction "point_1") (pintype "passive"))
      (node (ref "U5") (pin "N18") (pinfunction "IO_L13P_T2_MRCC_34_N18") (pintype "passive"))
    )
    (net (code "58") (name "/PLCLK_p") (class "Default")
      (node (ref "TP4") (pin "1") (pinfunction "point_1") (pintype "passive"))
      (node (ref "U5") (pin "P19") (pinfunction "IO_L13N_T2_MRCC_34_P19") (pintype "passive"))
    )
    (net (code "59") (name "/PROGRAM_B") (class "Default")
      (node (ref "R16") (pin "2") (pinfunction "2_2") (pintype "passive"))
      (node (ref "U5") (pin "L6") (pinfunction "PROGRAM_B_0_L6") (pintype "passive"))
    )
    (net (code "60") (name "/PSCLK") (class "Default")
      (node (ref "TP3") (pin "1") (pinfunction "point_1") (pintype "passive"))
      (node (ref "U5") (pin "E7") (pinfunction "PS_CLK_500_E7") (pintype "passive"))
    )
    (net (code "61") (name "/PSU1_RXD") (class "Default")
      (node (ref "U5") (pin "C5") (pinfunction "PS_MIO14_500_C5") (pintype "passive"))
    )
    (net (code "62") (name "/PSU1_TXD") (class "Default")
      (node (ref "U5") (pin "C8") (pinfunction "PS_MIO15_500_C8") (pintype "passive"))
    )
    (net (code "63") (name "/PSU2_RXD") (class "Default")
      (node (ref "U5") (pin "D9") (pinfunction "PS_MIO12_500_D9") (pintype "passive"))
    )
    (net (code "64") (name "/PSU2_TXD") (class "Default")
      (node (ref "U5") (pin "E8") (pinfunction "PS_MIO13_500_E8") (pintype "passive"))
    )
    (net (code "65") (name "/PS_POR_B") (class "Default")
      (node (ref "U5") (pin "C7") (pinfunction "PS_POR_B_500_C7") (pintype "passive"))
      (node (ref "U6") (pin "2") (pinfunction "!RESET_2") (pintype "passive"))
    )
    (net (code "66") (name "/QSPI_CLCOK") (class "Default")
      (node (ref "R14") (pin "1") (pinfunction "1_1") (pintype "passive"))
      (node (ref "U5") (pin "A5") (pinfunction "PS_MIO6_500_A5") (pintype "passive"))
    )
    (net (code "67") (name "/QSPI_CLK") (class "Default")
      (node (ref "R14") (pin "2") (pinfunction "2_2") (pintype "passive"))
      (node (ref "U8") (pin "6") (pinfunction "CLK_6") (pintype "passive"))
    )
    (net (code "68") (name "/QSPI_CS") (class "Default")
      (node (ref "U5") (pin "A7") (pinfunction "PS_MIO1_500_A7") (pintype "passive"))
      (node (ref "U8") (pin "1") (pinfunction "CS#_1") (pintype "passive"))
    )
    (net (code "69") (name "/QSPI_DQ0") (class "Default")
      (node (ref "U5") (pin "B8") (pinfunction "PS_MIO2_500_B8") (pintype "passive"))
      (node (ref "U8") (pin "5") (pinfunction "DI(IO0)_5") (pintype "passive"))
    )
    (net (code "70") (name "/QSPI_DQ1") (class "Default")
      (node (ref "U5") (pin "D6") (pinfunction "PS_MIO3_500_D6") (pintype "passive"))
      (node (ref "U8") (pin "2") (pinfunction "DO(IO1)_2") (pintype "passive"))
    )
    (net (code "71") (name "/QSPI_DQ2") (class "Default")
      (node (ref "R18") (pin "2") (pinfunction "2_2") (pintype "passive"))
      (node (ref "U5") (pin "B7") (pinfunction "PS_MIO4_500_B7") (pintype "passive"))
      (node (ref "U8") (pin "3") (pinfunction "IO2(WP#)_3") (pintype "passive"))
    )
    (net (code "72") (name "/QSPI_DQ3") (class "Default")
      (node (ref "R17") (pin "1") (pinfunction "1_1") (pintype "passive"))
      (node (ref "U5") (pin "A6") (pinfunction "PS_MIO5_500_A6") (pintype "passive"))
      (node (ref "U8") (pin "7") (pinfunction "IO3(HD/RST#)_7") (pintype "passive"))
    )
    (net (code "73") (name "/SRST") (class "Default")
      (node (ref "U5") (pin "B10") (pinfunction "PS_SRST_B_501_B10") (pintype "passive"))
    )
    (net (code "74") (name "/VCCPLL") (class "Default")
      (node (ref "FB2") (pin "1") (pinfunction "1_1") (pintype "passive"))
      (node (ref "U5") (pin "G8") (pinfunction "VCCPLL_G8") (pintype "passive"))
    )
    (net (code "75") (name "/VREF502") (class "Default")
      (node (ref "R12") (pin "1") (pinfunction "1_1") (pintype "passive"))
      (node (ref "R13") (pin "2") (pinfunction "2_2") (pintype "passive"))
      (node (ref "U5") (pin "H6") (pinfunction "PS_DDR_VREF0_502_H6") (pintype "passive"))
      (node (ref "U5") (pin "P6") (pinfunction "PS_DDR_VREF1_502_P6") (pintype "passive"))
    )
    (net (code "76") (name "/VREF_501") (class "Default")
      (node (ref "R21") (pin "1") (pinfunction "1_1") (pintype "passive"))
      (node (ref "R22") (pin "2") (pinfunction "2_2") (pintype "passive"))
      (node (ref "U5") (pin "E11") (pinfunction "PS_MIO_VREF_501_E11") (pintype "passive"))
    )
    (net (code "77") (name "/ZQ") (class "Default")
      (node (ref "R23") (pin "1") (pinfunction "1_1") (pintype "passive"))
      (node (ref "U7") (pin "L8") (pinfunction "ZQ_L8") (pintype "passive"))
    )
    (net (code "78") (name "GND") (class "Default")
      (node (ref "C26") (pin "1") (pinfunction "1_1") (pintype "passive"))
      (node (ref "C27") (pin "1") (pinfunction "1_1") (pintype "passive"))
      (node (ref "C28") (pin "1") (pinfunction "1_1") (pintype "passive"))
      (node (ref "C29") (pin "1") (pinfunction "1_1") (pintype "passive"))
      (node (ref "C30") (pin "1") (pinfunction "1_1") (pintype "passive"))
      (node (ref "C31") (pin "1") (pinfunction "1_1") (pintype "passive"))
      (node (ref "C32") (pin "1") (pinfunction "1_1") (pintype "passive"))
      (node (ref "C33") (pin "1") (pinfunction "1_1") (pintype "passive"))
      (node (ref "C34") (pin "1") (pinfunction "1_1") (pintype "passive"))
      (node (ref "C35") (pin "1") (pinfunction "1_1") (pintype "passive"))
      (node (ref "C36") (pin "1") (pinfunction "1_1") (pintype "passive"))
      (node (ref "C37") (pin "1") (pinfunction "1_1") (pintype "passive"))
      (node (ref "C38") (pin "1") (pinfunction "1_1") (pintype "passive"))
      (node (ref "C39") (pin "1") (pinfunction "1_1") (pintype "passive"))
      (node (ref "C40") (pin "1") (pinfunction "1_1") (pintype "passive"))
      (node (ref "C41") (pin "1") (pinfunction "1_1") (pintype "passive"))
      (node (ref "C42") (pin "1") (pinfunction "1_1") (pintype "passive"))
      (node (ref "C43") (pin "1") (pinfunction "1_1") (pintype "passive"))
      (node (ref "C44") (pin "1") (pinfunction "1_1") (pintype "passive"))
      (node (ref "C45") (pin "1") (pinfunction "1_1") (pintype "passive"))
      (node (ref "C46") (pin "1") (pinfunction "1_1") (pintype "passive"))
      (node (ref "C47") (pin "1") (pinfunction "1_1") (pintype "passive"))
      (node (ref "C48") (pin "1") (pinfunction "1_1") (pintype "passive"))
      (node (ref "C49") (pin "1") (pinfunction "1_1") (pintype "passive"))
      (node (ref "C50") (pin "1") (pinfunction "1_1") (pintype "passive"))
      (node (ref "C51") (pin "1") (pinfunction "1_1") (pintype "passive"))
      (node (ref "C52") (pin "1") (pinfunction "1_1") (pintype "passive"))
      (node (ref "C53") (pin "1") (pinfunction "1_1") (pintype "passive"))
      (node (ref "C54") (pin "1") (pinfunction "1_1") (pintype "passive"))
      (node (ref "C55") (pin "1") (pinfunction "1_1") (pintype "passive"))
      (node (ref "C56") (pin "1") (pinfunction "1_1") (pintype "passive"))
      (node (ref "C57") (pin "1") (pinfunction "1_1") (pintype "passive"))
      (node (ref "C58") (pin "1") (pinfunction "1_1") (pintype "passive"))
      (node (ref "C59") (pin "1") (pinfunction "1_1") (pintype "passive"))
      (node (ref "C60") (pin "1") (pinfunction "1_1") (pintype "passive"))
      (node (ref "C61") (pin "1") (pinfunction "1_1") (pintype "passive"))
      (node (ref "C62") (pin "1") (pinfunction "1_1") (pintype "passive"))
      (node (ref "C63") (pin "1") (pinfunction "1_1") (pintype "passive"))
      (node (ref "C64") (pin "1") (pinfunction "1_1") (pintype "passive"))
      (node (ref "C65") (pin "1") (pinfunction "1_1") (pintype "passive"))
      (node (ref "C66") (pin "1") (pinfunction "1_1") (pintype "passive"))
      (node (ref "C67") (pin "1") (pinfunction "1_1") (pintype "passive"))
      (node (ref "C68") (pin "1") (pinfunction "1_1") (pintype "passive"))
      (node (ref "C69") (pin "1") (pinfunction "1_1") (pintype "passive"))
      (node (ref "C70") (pin "1") (pinfunction "1_1") (pintype "passive"))
      (node (ref "C71") (pin "1") (pinfunction "1_1") (pintype "passive"))
      (node (ref "C72") (pin "1") (pinfunction "1_1") (pintype "passive"))
      (node (ref "C73") (pin "1") (pinfunction "1_1") (pintype "passive"))
      (node (ref "C74") (pin "1") (pinfunction "1_1") (pintype "passive"))
      (node (ref "C75") (pin "1") (pinfunction "1_1") (pintype "passive"))
      (node (ref "C76") (pin "1") (pinfunction "1_1") (pintype "passive"))
      (node (ref "C77") (pin "1") (pinfunction "1_1") (pintype "passive"))
      (node (ref "C78") (pin "1") (pinfunction "1_1") (pintype "passive"))
      (node (ref "C79") (pin "1") (pinfunction "1_1") (pintype "passive"))
      (node (ref "C80") (pin "1") (pinfunction "1_1") (pintype "passive"))
      (node (ref "C81") (pin "1") (pinfunction "1_1") (pintype "passive"))
      (node (ref "C82") (pin "1") (pinfunction "1_1") (pintype "passive"))
      (node (ref "R13") (pin "1") (pinfunction "1_1") (pintype "passive"))
      (node (ref "R19") (pin "1") (pinfunction "1_1") (pintype "passive"))
      (node (ref "R20") (pin "1") (pinfunction "1_1") (pintype "passive"))
      (node (ref "R22") (pin "1") (pinfunction "1_1") (pintype "passive"))
      (node (ref "R24") (pin "1") (pinfunction "1_1") (pintype "passive"))
      (node (ref "R25") (pin "1") (pinfunction "1_1") (pintype "passive"))
      (node (ref "R28") (pin "1") (pinfunction "1_1") (pintype "passive"))
      (node (ref "S4") (pin "1") (pinfunction "1_1") (pintype "passive"))
      (node (ref "U5") (pin "A18") (pinfunction "GND_A18") (pintype "passive"))
      (node (ref "U5") (pin "A8") (pinfunction "GND_A8") (pintype "passive"))
      (node (ref "U5") (pin "B1") (pinfunction "GND_B1") (pintype "passive"))
      (node (ref "U5") (pin "B11") (pinfunction "GND_B11") (pintype "passive"))
      (node (ref "U5") (pin "C14") (pinfunction "GND_C14") (pintype "passive"))
      (node (ref "U5") (pin "C4") (pinfunction "GND_C4") (pintype "passive"))
      (node (ref "U5") (pin "C9") (pinfunction "GND_C9") (pintype "passive"))
      (node (ref "U5") (pin "D17") (pinfunction "GND_D17") (pintype "passive"))
      (node (ref "U5") (pin "E10") (pinfunction "GND_E10") (pintype "passive"))
      (node (ref "U5") (pin "E20") (pinfunction "GND_E20") (pintype "passive"))
      (node (ref "U5") (pin "F10") (pinfunction "RSVDGND_F10") (pintype "passive"))
      (node (ref "U5") (pin "F3") (pinfunction "GND_F3") (pintype "passive"))
      (node (ref "U5") (pin "F7") (pinfunction "GND_F7") (pintype "passive"))
      (node (ref "U5") (pin "G10") (pinfunction "GND_G10") (pintype "passive"))
      (node (ref "U5") (pin "G12") (pinfunction "GND_G12") (pintype "passive"))
      (node (ref "U5") (pin "G16") (pinfunction "GND_G16") (pintype "passive"))
      (node (ref "U5") (pin "H11") (pinfunction "GND_H11") (pintype "passive"))
      (node (ref "U5") (pin "H13") (pinfunction "GND_H13") (pintype "passive"))
      (node (ref "U5") (pin "H19") (pinfunction "GND_H19") (pintype "passive"))
      (node (ref "U5") (pin "H7") (pinfunction "GND_H7") (pintype "passive"))
      (node (ref "U5") (pin "H9") (pinfunction "GND_H9") (pintype "passive"))
      (node (ref "U5") (pin "J10") (pinfunction "GNDADC_0_J10") (pintype "passive"))
      (node (ref "U5") (pin "J12") (pinfunction "GND_J12") (pintype "passive"))
      (node (ref "U5") (pin "J2") (pinfunction "GND_J2") (pintype "passive"))
      (node (ref "U5") (pin "J8") (pinfunction "GND_J8") (pintype "passive"))
      (node (ref "U5") (pin "K10") (pinfunction "VREFN_0_K10") (pintype "passive"))
      (node (ref "U5") (pin "K11") (pinfunction "GND_K11") (pintype "passive"))
      (node (ref "U5") (pin "K13") (pinfunction "GND_K13") (pintype "passive"))
      (node (ref "U5") (pin "K15") (pinfunction "GND_K15") (pintype "passive"))
      (node (ref "U5") (pin "K5") (pinfunction "GND_K5") (pintype "passive"))
      (node (ref "U5") (pin "K7") (pinfunction "GND_K7") (pintype "passive"))
      (node (ref "U5") (pin "L12") (pinfunction "GND_L12") (pintype "passive"))
      (node (ref "U5") (pin "L18") (pinfunction "GND_L18") (pintype "passive"))
      (node (ref "U5") (pin "L8") (pinfunction "GND_L8") (pintype "passive"))
      (node (ref "U5") (pin "L9") (pinfunction "VREFP_0_L9") (pintype "passive"))
      (node (ref "U5") (pin "M1") (pinfunction "GND_M1") (pintype "passive"))
      (node (ref "U5") (pin "M10") (pinfunction "DXN_0_M10") (pintype "passive"))
      (node (ref "U5") (pin "M11") (pinfunction "GND_M11") (pintype "passive"))
      (node (ref "U5") (pin "M13") (pinfunction "GND_M13") (pintype "passive"))
      (node (ref "U5") (pin "M7") (pinfunction "GND_M7") (pintype "passive"))
      (node (ref "U5") (pin "M9") (pinfunction "DXP_0_M9") (pintype "passive"))
      (node (ref "U5") (pin "N10") (pinfunction "GND_N10") (pintype "passive"))
      (node (ref "U5") (pin "N12") (pinfunction "GND_N12") (pintype "passive"))
      (node (ref "U5") (pin "N14") (pinfunction "GND_N14") (pintype "passive"))
      (node (ref "U5") (pin "N4") (pinfunction "GND_N4") (pintype "passive"))
      (node (ref "U5") (pin "N8") (pinfunction "GND_N8") (pintype "passive"))
      (node (ref "U5") (pin "P11") (pinfunction "GND_P11") (pintype "passive"))
      (node (ref "U5") (pin "P13") (pinfunction "GND_P13") (pintype "passive"))
      (node (ref "U5") (pin "P17") (pinfunction "GND_P17") (pintype "passive"))
      (node (ref "U5") (pin "P7") (pinfunction "GND_P7") (pintype "passive"))
      (node (ref "U5") (pin "P9") (pinfunction "GND_P9") (pintype "passive"))
      (node (ref "U5") (pin "R12") (pinfunction "GND_R12") (pintype "passive"))
      (node (ref "U5") (pin "R20") (pinfunction "GND_R20") (pintype "passive"))
      (node (ref "U5") (pin "R8") (pinfunction "GND_R8") (pintype "passive"))
      (node (ref "U5") (pin "T13") (pinfunction "GND_T13") (pintype "passive"))
      (node (ref "U5") (pin "T3") (pinfunction "GND_T3") (pintype "passive"))
      (node (ref "U5") (pin "T7") (pinfunction "GND_T7") (pintype "passive"))
      (node (ref "U5") (pin "U16") (pinfunction "GND_U16") (pintype "passive"))
      (node (ref "U5") (pin "U6") (pinfunction "GND_U6") (pintype "passive"))
      (node (ref "U5") (pin "V19") (pinfunction "GND_V19") (pintype "passive"))
      (node (ref "U5") (pin "V9") (pinfunction "GND_V9") (pintype "passive"))
      (node (ref "U5") (pin "W12") (pinfunction "GND_W12") (pintype "passive"))
      (node (ref "U5") (pin "W2") (pinfunction "GND_W2") (pintype "passive"))
      (node (ref "U5") (pin "Y15") (pinfunction "GND_Y15") (pintype "passive"))
      (node (ref "U5") (pin "Y5") (pinfunction "GND_Y5") (pintype "passive"))
      (node (ref "U6") (pin "1") (pinfunction "GND_1") (pintype "passive"))
      (node (ref "U7") (pin "A9") (pinfunction "VSS_A9") (pintype "passive"))
      (node (ref "U7") (pin "B1") (pinfunction "VSSQ_B1") (pintype "passive"))
      (node (ref "U7") (pin "B3") (pinfunction "VSS_B3") (pintype "passive"))
      (node (ref "U7") (pin "B9") (pinfunction "VSSQ_B9") (pintype "passive"))
      (node (ref "U7") (pin "D1") (pinfunction "VSSQ_D1") (pintype "passive"))
      (node (ref "U7") (pin "D8") (pinfunction "VSSQ_D8") (pintype "passive"))
      (node (ref "U7") (pin "E1") (pinfunction "VSS_E1") (pintype "passive"))
      (node (ref "U7") (pin "E2") (pinfunction "VSSQ_E2") (pintype "passive"))
      (node (ref "U7") (pin "E8") (pinfunction "VSSQ_E8") (pintype "passive"))
      (node (ref "U7") (pin "F9") (pinfunction "VSSQ_F9") (pintype "passive"))
      (node (ref "U7") (pin "G1") (pinfunction "VSSQ_G1") (pintype "passive"))
      (node (ref "U7") (pin "G8") (pinfunction "VSS_G8") (pintype "passive"))
      (node (ref "U7") (pin "G9") (pinfunction "VSSQ_G9") (pintype "passive"))
      (node (ref "U7") (pin "J2") (pinfunction "VSS_J2") (pintype "passive"))
      (node (ref "U7") (pin "J8") (pinfunction "VSS_J8") (pintype "passive"))
      (node (ref "U7") (pin "M1") (pinfunction "VSS_M1") (pintype "passive"))
      (node (ref "U7") (pin "M9") (pinfunction "VSS_M9") (pintype "passive"))
      (node (ref "U7") (pin "P1") (pinfunction "VSS_P1") (pintype "passive"))
      (node (ref "U7") (pin "P9") (pinfunction "VSS_P9") (pintype "passive"))
      (node (ref "U7") (pin "T1") (pinfunction "VSS_T1") (pintype "passive"))
      (node (ref "U7") (pin "T9") (pinfunction "VSS_T9") (pintype "passive"))
      (node (ref "U8") (pin "4") (pinfunction "GND_4") (pintype "passive"))
      (node (ref "U8") (pin "9") (pinfunction "EP_9") (pintype "passive"))
    )
    (net (code "79") (name "Net-(D1-PadA)") (class "Default")
      (node (ref "D1") (pin "A") (pinfunction "A_A") (pintype "passive"))
      (node (ref "R26") (pin "1") (pinfunction "1_1") (pintype "passive"))
    )
    (net (code "80") (name "Net-(R23-Pad2)") (class "Default")
      (node (ref "R23") (pin "2") (pinfunction "2_2") (pintype "passive"))
      (node (ref "R25") (pin "2") (pinfunction "2_2") (pintype "passive"))
    )
    (net (code "81") (name "Net-(S3-B1)") (class "Default")
      (node (ref "R18") (pin "1") (pinfunction "1_1") (pintype "passive"))
      (node (ref "R20") (pin "2") (pinfunction "2_2") (pintype "passive"))
      (node (ref "S3") (pin "4") (pinfunction "B1_4") (pintype "passive"))
    )
    (net (code "82") (name "Net-(S3-B2)") (class "Default")
      (node (ref "R17") (pin "2") (pinfunction "2_2") (pintype "passive"))
      (node (ref "R19") (pin "2") (pinfunction "2_2") (pintype "passive"))
      (node (ref "S3") (pin "3") (pinfunction "B2_3") (pintype "passive"))
    )
    (net (code "83") (name "Net-(U5C-PS_DDR_VRN_502)") (class "Default")
      (node (ref "R27") (pin "2") (pinfunction "2_2") (pintype "passive"))
      (node (ref "U5") (pin "G5") (pinfunction "PS_DDR_VRN_502_G5") (pintype "passive"))
    )
    (net (code "84") (name "Net-(U5C-PS_DDR_VRP_502)") (class "Default")
      (node (ref "R28") (pin "2") (pinfunction "2_2") (pintype "passive"))
      (node (ref "U5") (pin "H5") (pinfunction "PS_DDR_VRP_502_H5") (pintype "passive"))
    )
    (net (code "85") (name "Net-(U6-!MR)") (class "Default")
      (node (ref "S4") (pin "2") (pinfunction "2_2") (pintype "passive"))
      (node (ref "U6") (pin "3") (pinfunction "!MR_3") (pintype "passive"))
    )
    (net (code "86") (name "VCC_1V0") (class "Default")
      (node (ref "C26") (pin "2") (pinfunction "2_2") (pintype "passive"))
      (node (ref "C27") (pin "2") (pinfunction "2_2") (pintype "passive"))
      (node (ref "C28") (pin "2") (pinfunction "2_2") (pintype "passive"))
      (node (ref "C29") (pin "2") (pinfunction "2_2") (pintype "passive"))
      (node (ref "C30") (pin "2") (pinfunction "2_2") (pintype "passive"))
      (node (ref "C31") (pin "2") (pinfunction "2_2") (pintype "passive"))
      (node (ref "C32") (pin "2") (pinfunction "2_2") (pintype "passive"))
      (node (ref "C33") (pin "2") (pinfunction "2_2") (pintype "passive"))
      (node (ref "C34") (pin "2") (pinfunction "2_2") (pintype "passive"))
      (node (ref "C35") (pin "2") (pinfunction "2_2") (pintype "passive"))
      (node (ref "U5") (pin "G11") (pinfunction "VCCBRAM_G11") (pintype "passive"))
      (node (ref "U5") (pin "G13") (pinfunction "VCCINT_G13") (pintype "passive"))
      (node (ref "U5") (pin "G7") (pinfunction "VCCPINT_G7") (pintype "passive"))
      (node (ref "U5") (pin "H10") (pinfunction "VCCBRAM_H10") (pintype "passive"))
      (node (ref "U5") (pin "H12") (pinfunction "VCCINT_H12") (pintype "passive"))
      (node (ref "U5") (pin "J13") (pinfunction "VCCINT_J13") (pintype "passive"))
      (node (ref "U5") (pin "J7") (pinfunction "VCCPINT_J7") (pintype "passive"))
      (node (ref "U5") (pin "K12") (pinfunction "VCCINT_K12") (pintype "passive"))
      (node (ref "U5") (pin "L13") (pinfunction "VCCINT_L13") (pintype "passive"))
      (node (ref "U5") (pin "L7") (pinfunction "VCCPINT_L7") (pintype "passive"))
      (node (ref "U5") (pin "M12") (pinfunction "VCCINT_M12") (pintype "passive"))
      (node (ref "U5") (pin "N13") (pinfunction "VCCINT_N13") (pintype "passive"))
      (node (ref "U5") (pin "N7") (pinfunction "VCCPINT_N7") (pintype "passive"))
      (node (ref "U5") (pin "P12") (pinfunction "VCCINT_P12") (pintype "passive"))
      (node (ref "U5") (pin "P8") (pinfunction "VCCPINT_P8") (pintype "passive"))
      (node (ref "U5") (pin "R13") (pinfunction "VCCINT_R13") (pintype "passive"))
      (node (ref "U5") (pin "R7") (pinfunction "VCCPINT_R7") (pintype "passive"))
    )
    (net (code "87") (name "VCC_1V5") (class "Default")
      (node (ref "C72") (pin "2") (pinfunction "2_2") (pintype "passive"))
      (node (ref "C73") (pin "2") (pinfunction "2_2") (pintype "passive"))
      (node (ref "C74") (pin "2") (pinfunction "2_2") (pintype "passive"))
      (node (ref "C75") (pin "2") (pinfunction "2_2") (pintype "passive"))
      (node (ref "C76") (pin "2") (pinfunction "2_2") (pintype "passive"))
      (node (ref "C77") (pin "2") (pinfunction "2_2") (pintype "passive"))
      (node (ref "C78") (pin "2") (pinfunction "2_2") (pintype "passive"))
      (node (ref "C79") (pin "2") (pinfunction "2_2") (pintype "passive"))
      (node (ref "C80") (pin "2") (pinfunction "2_2") (pintype "passive"))
      (node (ref "C81") (pin "2") (pinfunction "2_2") (pintype "passive"))
      (node (ref "R12") (pin "2") (pinfunction "2_2") (pintype "passive"))
      (node (ref "R27") (pin "1") (pinfunction "1_1") (pintype "passive"))
      (node (ref "U5") (pin "A3") (pinfunction "VCCO_DDR_502_A3") (pintype "passive"))
      (node (ref "U5") (pin "D2") (pinfunction "VCCO_DDR_502_D2") (pintype "passive"))
      (node (ref "U5") (pin "E5") (pinfunction "VCCO_DDR_502_E5") (pintype "passive"))
      (node (ref "U5") (pin "G1") (pinfunction "VCCO_DDR_502_G1") (pintype "passive"))
      (node (ref "U5") (pin "H4") (pinfunction "VCCO_DDR_502_H4") (pintype "passive"))
      (node (ref "U5") (pin "L3") (pinfunction "VCCO_DDR_502_L3") (pintype "passive"))
      (node (ref "U5") (pin "P2") (pinfunction "VCCO_DDR_502_P2") (pintype "passive"))
      (node (ref "U5") (pin "R5") (pinfunction "VCCO_DDR_502_R5") (pintype "passive"))
      (node (ref "U5") (pin "U1") (pinfunction "VCCO_DDR_502_U1") (pintype "passive"))
      (node (ref "U5") (pin "V4") (pinfunction "VCCO_DDR_502_V4") (pintype "passive"))
      (node (ref "U7") (pin "A1") (pinfunction "VDDQ_A1") (pintype "passive"))
      (node (ref "U7") (pin "A8") (pinfunction "VDDQ_A8") (pintype "passive"))
      (node (ref "U7") (pin "B2") (pinfunction "VDD_B2") (pintype "passive"))
      (node (ref "U7") (pin "C1") (pinfunction "VDDQ_C1") (pintype "passive"))
      (node (ref "U7") (pin "C9") (pinfunction "VDDQ_C9") (pintype "passive"))
      (node (ref "U7") (pin "D2") (pinfunction "VDDQ_D2") (pintype "passive"))
      (node (ref "U7") (pin "D9") (pinfunction "VDD_D9") (pintype "passive"))
      (node (ref "U7") (pin "E9") (pinfunction "VDDQ_E9") (pintype "passive"))
      (node (ref "U7") (pin "F1") (pinfunction "VDDQ_F1") (pintype "passive"))
      (node (ref "U7") (pin "G7") (pinfunction "VDD_G7") (pintype "passive"))
      (node (ref "U7") (pin "H2") (pinfunction "VDDQ_H2") (pintype "passive"))
      (node (ref "U7") (pin "H9") (pinfunction "VDDQ_H9") (pintype "passive"))
      (node (ref "U7") (pin "K2") (pinfunction "VDD_K2") (pintype "passive"))
      (node (ref "U7") (pin "K8") (pinfunction "VDD_K8") (pintype "passive"))
      (node (ref "U7") (pin "N1") (pinfunction "VDD_N1") (pintype "passive"))
      (node (ref "U7") (pin "N9") (pinfunction "VDD_N9") (pintype "passive"))
      (node (ref "U7") (pin "R1") (pinfunction "VDD_R1") (pintype "passive"))
      (node (ref "U7") (pin "R9") (pinfunction "VDD_R9") (pintype "passive"))
    )
    (net (code "88") (name "VCC_1V8") (class "Default")
      (node (ref "C36") (pin "2") (pinfunction "2_2") (pintype "passive"))
      (node (ref "C37") (pin "2") (pinfunction "2_2") (pintype "passive"))
      (node (ref "C38") (pin "2") (pinfunction "2_2") (pintype "passive"))
      (node (ref "C39") (pin "2") (pinfunction "2_2") (pintype "passive"))
      (node (ref "C40") (pin "2") (pinfunction "2_2") (pintype "passive"))
      (node (ref "C41") (pin "2") (pinfunction "2_2") (pintype "passive"))
      (node (ref "C42") (pin "2") (pinfunction "2_2") (pintype "passive"))
      (node (ref "C43") (pin "2") (pinfunction "2_2") (pintype "passive"))
      (node (ref "C44") (pin "2") (pinfunction "2_2") (pintype "passive"))
      (node (ref "C45") (pin "2") (pinfunction "2_2") (pintype "passive"))
      (node (ref "C46") (pin "2") (pinfunction "2_2") (pintype "passive"))
      (node (ref "C47") (pin "2") (pinfunction "2_2") (pintype "passive"))
      (node (ref "C48") (pin "2") (pinfunction "2_2") (pintype "passive"))
      (node (ref "C49") (pin "2") (pinfunction "2_2") (pintype "passive"))
      (node (ref "C50") (pin "2") (pinfunction "2_2") (pintype "passive"))
      (node (ref "FB2") (pin "2") (pinfunction "2_2") (pintype "passive"))
      (node (ref "R21") (pin "2") (pinfunction "2_2") (pintype "passive"))
      (node (ref "U5") (pin "A13") (pinfunction "VCCO_MIO1_501_A13") (pintype "passive"))
      (node (ref "U5") (pin "B16") (pinfunction "VCCO_MIO1_501_B16") (pintype "passive"))
      (node (ref "U5") (pin "D12") (pinfunction "VCCO_MIO1_501_D12") (pintype "passive"))
      (node (ref "U5") (pin "E15") (pinfunction "VCCO_MIO1_501_E15") (pintype "passive"))
      (node (ref "U5") (pin "F11") (pinfunction "VCCBATT_0_F11") (pintype "passive"))
      (node (ref "U5") (pin "F8") (pinfunction "VCCPAUX_F8") (pintype "passive"))
      (node (ref "U5") (pin "G9") (pinfunction "VCCPAUX_G9") (pintype "passive"))
      (node (ref "U5") (pin "H8") (pinfunction "VCCPAUX_H8") (pintype "passive"))
      (node (ref "U5") (pin "J11") (pinfunction "VCCAUX_J11") (pintype "passive"))
      (node (ref "U5") (pin "J9") (pinfunction "VCCADC_0_J9") (pintype "passive"))
      (node (ref "U5") (pin "K8") (pinfunction "VCCPAUX_K8") (pintype "passive"))
      (node (ref "U5") (pin "L11") (pinfunction "VCCAUX_L11") (pintype "passive"))
      (node (ref "U5") (pin "M8") (pinfunction "VCCPAUX_M8") (pintype "passive"))
      (node (ref "U5") (pin "N11") (pinfunction "VCCAUX_N11") (pintype "passive"))
      (node (ref "U5") (pin "N9") (pinfunction "VCCAUX_N9") (pintype "passive"))
      (node (ref "U5") (pin "P10") (pinfunction "VCCAUX_P10") (pintype "passive"))
      (node (ref "U5") (pin "R9") (pinfunction "VCCAUX_R9") (pintype "passive"))
    )
    (net (code "89") (name "VCC_3V3") (class "Default")
      (node (ref "C51") (pin "2") (pinfunction "2_2") (pintype "passive"))
      (node (ref "C52") (pin "2") (pinfunction "2_2") (pintype "passive"))
      (node (ref "C53") (pin "2") (pinfunction "2_2") (pintype "passive"))
      (node (ref "C54") (pin "2") (pinfunction "2_2") (pintype "passive"))
      (node (ref "C55") (pin "2") (pinfunction "2_2") (pintype "passive"))
      (node (ref "C56") (pin "2") (pinfunction "2_2") (pintype "passive"))
      (node (ref "C57") (pin "2") (pinfunction "2_2") (pintype "passive"))
      (node (ref "C58") (pin "2") (pinfunction "2_2") (pintype "passive"))
      (node (ref "C59") (pin "2") (pinfunction "2_2") (pintype "passive"))
      (node (ref "C60") (pin "2") (pinfunction "2_2") (pintype "passive"))
      (node (ref "C61") (pin "2") (pinfunction "2_2") (pintype "passive"))
      (node (ref "C62") (pin "2") (pinfunction "2_2") (pintype "passive"))
      (node (ref "C63") (pin "2") (pinfunction "2_2") (pintype "passive"))
      (node (ref "C64") (pin "2") (pinfunction "2_2") (pintype "passive"))
      (node (ref "C65") (pin "2") (pinfunction "2_2") (pintype "passive"))
      (node (ref "C66") (pin "2") (pinfunction "2_2") (pintype "passive"))
      (node (ref "C67") (pin "2") (pinfunction "2_2") (pintype "passive"))
      (node (ref "C68") (pin "2") (pinfunction "2_2") (pintype "passive"))
      (node (ref "C69") (pin "2") (pinfunction "2_2") (pintype "passive"))
      (node (ref "C70") (pin "2") (pinfunction "2_2") (pintype "passive"))
      (node (ref "C71") (pin "2") (pinfunction "2_2") (pintype "passive"))
      (node (ref "C82") (pin "2") (pinfunction "2_2") (pintype "passive"))
      (node (ref "R15") (pin "1") (pinfunction "1_1") (pintype "passive"))
      (node (ref "R16") (pin "1") (pinfunction "1_1") (pintype "passive"))
      (node (ref "R26") (pin "2") (pinfunction "2_2") (pintype "passive"))
      (node (ref "S3") (pin "1") (pinfunction "A1_1") (pintype "passive"))
      (node (ref "S3") (pin "2") (pinfunction "A2_2") (pintype "passive"))
      (node (ref "U5") (pin "B6") (pinfunction "VCCO_MIO0_500_B6") (pintype "passive"))
      (node (ref "U5") (pin "C19") (pinfunction "VCCO_35_C19") (pintype "passive"))
      (node (ref "U5") (pin "D7") (pinfunction "VCCO_MIO0_500_D7") (pintype "passive"))
      (node (ref "U5") (pin "F18") (pinfunction "VCCO_35_F18") (pintype "passive"))
      (node (ref "U5") (pin "H14") (pinfunction "VCCO_35_H14") (pintype "passive"))
      (node (ref "U5") (pin "J17") (pinfunction "VCCO_35_J17") (pintype "passive"))
      (node (ref "U5") (pin "K20") (pinfunction "VCCO_35_K20") (pintype "passive"))
      (node (ref "U5") (pin "K6") (pinfunction "VCCO_0_K6") (pintype "passive"))
      (node (ref "U5") (pin "M16") (pinfunction "VCCO_35_M16") (pintype "passive"))
      (node (ref "U5") (pin "M6") (pinfunction "CFGBVS_0_M6") (pintype "passive"))
      (node (ref "U5") (pin "N19") (pinfunction "VCCO_34_N19") (pintype "passive"))
      (node (ref "U5") (pin "N6") (pinfunction "RSVDVCC3_N6") (pintype "passive"))
      (node (ref "U5") (pin "R15") (pinfunction "VCCO_34_R15") (pintype "passive"))
      (node (ref "U5") (pin "R6") (pinfunction "RSVDVCC2_R6") (pintype "passive"))
      (node (ref "U5") (pin "T18") (pinfunction "VCCO_34_T18") (pintype "passive"))
      (node (ref "U5") (pin "T6") (pinfunction "RSVDVCC1_T6") (pintype "passive"))
      (node (ref "U5") (pin "T8") (pinfunction "VCCO_13_T8") (pintype "passive"))
      (node (ref "U5") (pin "U11") (pinfunction "VCCO_13_U11") (pintype "passive"))
      (node (ref "U5") (pin "V14") (pinfunction "VCCO_34_V14") (pintype "passive"))
      (node (ref "U5") (pin "W17") (pinfunction "VCCO_34_W17") (pintype "passive"))
      (node (ref "U5") (pin "W7") (pinfunction "VCCO_13_W7") (pintype "passive"))
      (node (ref "U5") (pin "Y10") (pinfunction "VCCO_13_Y10") (pintype "passive"))
      (node (ref "U5") (pin "Y20") (pinfunction "VCCO_34_Y20") (pintype "passive"))
      (node (ref "U6") (pin "4") (pinfunction "VCC_4") (pintype "passive"))
      (node (ref "U8") (pin "8") (pinfunction "VCC_8") (pintype "passive"))
    )
    (net (code "90") (name "VREF_DDR") (class "Default")
      (node (ref "U7") (pin "H1") (pinfunction "VREFDQ_H1") (pintype "passive"))
      (node (ref "U7") (pin "M8") (pinfunction "VREFCA_M8") (pintype "passive"))
    )
    (net (code "91") (name "unconnected-(U5A-IO_0_34-PadR19)") (class "Default")
      (node (ref "U5") (pin "R19") (pinfunction "IO_0_34_R19") (pintype "passive"))
    )
    (net (code "92") (name "unconnected-(U5A-IO_0_35-PadG14)") (class "Default")
      (node (ref "U5") (pin "G14") (pinfunction "IO_0_35_G14") (pintype "passive"))
    )
    (net (code "93") (name "unconnected-(U5A-IO_25_34-PadT19)") (class "Default")
      (node (ref "U5") (pin "T19") (pinfunction "IO_25_34_T19") (pintype "passive"))
    )
    (net (code "94") (name "unconnected-(U5A-IO_25_35-PadJ15)") (class "Default")
      (node (ref "U5") (pin "J15") (pinfunction "IO_25_35_J15") (pintype "passive"))
    )
    (net (code "95") (name "unconnected-(U5A-IO_L1N_T0_34-PadT10)") (class "Default")
      (node (ref "U5") (pin "T10") (pinfunction "IO_L1N_T0_34_T10") (pintype "passive"))
    )
    (net (code "96") (name "unconnected-(U5A-IO_L1N_T0_AD0N_35-PadB20)") (class "Default")
      (node (ref "U5") (pin "B20") (pinfunction "IO_L1N_T0_AD0N_35_B20") (pintype "passive"))
    )
    (net (code "97") (name "unconnected-(U5A-IO_L1P_T0_34-PadT11)") (class "Default")
      (node (ref "U5") (pin "T11") (pinfunction "IO_L1P_T0_34_T11") (pintype "passive"))
    )
    (net (code "98") (name "unconnected-(U5A-IO_L1P_T0_AD0P_35-PadC20)") (class "Default")
      (node (ref "U5") (pin "C20") (pinfunction "IO_L1P_T0_AD0P_35_C20") (pintype "passive"))
    )
    (net (code "99") (name "unconnected-(U5A-IO_L2N_T0_34-PadU12)") (class "Default")
      (node (ref "U5") (pin "U12") (pinfunction "IO_L2N_T0_34_U12") (pintype "passive"))
    )
    (net (code "100") (name "unconnected-(U5A-IO_L2N_T0_AD8N_35-PadA20)") (class "Default")
      (node (ref "U5") (pin "A20") (pinfunction "IO_L2N_T0_AD8N_35_A20") (pintype "passive"))
    )
    (net (code "101") (name "unconnected-(U5A-IO_L2P_T0_34-PadT12)") (class "Default")
      (node (ref "U5") (pin "T12") (pinfunction "IO_L2P_T0_34_T12") (pintype "passive"))
    )
    (net (code "102") (name "unconnected-(U5A-IO_L2P_T0_AD8P_35-PadB19)") (class "Default")
      (node (ref "U5") (pin "B19") (pinfunction "IO_L2P_T0_AD8P_35_B19") (pintype "passive"))
    )
    (net (code "103") (name "unconnected-(U5A-IO_L3N_T0_DQS_34-PadV13)") (class "Default")
      (node (ref "U5") (pin "V13") (pinfunction "IO_L3N_T0_DQS_34_V13") (pintype "passive"))
    )
    (net (code "104") (name "unconnected-(U5A-IO_L3N_T0_DQS_AD1N_35-PadD18)") (class "Default")
      (node (ref "U5") (pin "D18") (pinfunction "IO_L3N_T0_DQS_AD1N_35_D18") (pintype "passive"))
    )
    (net (code "105") (name "unconnected-(U5A-IO_L3P_T0_DQS_AD1P_35-PadE17)") (class "Default")
      (node (ref "U5") (pin "E17") (pinfunction "IO_L3P_T0_DQS_AD1P_35_E17") (pintype "passive"))
    )
    (net (code "106") (name "unconnected-(U5A-IO_L3P_T0_DQS_PUDC_B_34-PadU13)") (class "Default")
      (node (ref "U5") (pin "U13") (pinfunction "IO_L3P_T0_DQS_PUDC_B_34_U13") (pintype "passive"))
    )
    (net (code "107") (name "unconnected-(U5A-IO_L4N_T0_34-PadW13)") (class "Default")
      (node (ref "U5") (pin "W13") (pinfunction "IO_L4N_T0_34_W13") (pintype "passive"))
    )
    (net (code "108") (name "unconnected-(U5A-IO_L4N_T0_35-PadD20)") (class "Default")
      (node (ref "U5") (pin "D20") (pinfunction "IO_L4N_T0_35_D20") (pintype "passive"))
    )
    (net (code "109") (name "unconnected-(U5A-IO_L4P_T0_34-PadV12)") (class "Default")
      (node (ref "U5") (pin "V12") (pinfunction "IO_L4P_T0_34_V12") (pintype "passive"))
    )
    (net (code "110") (name "unconnected-(U5A-IO_L4P_T0_35-PadD19)") (class "Default")
      (node (ref "U5") (pin "D19") (pinfunction "IO_L4P_T0_35_D19") (pintype "passive"))
    )
    (net (code "111") (name "unconnected-(U5A-IO_L5N_T0_34-PadT15)") (class "Default")
      (node (ref "U5") (pin "T15") (pinfunction "IO_L5N_T0_34_T15") (pintype "passive"))
    )
    (net (code "112") (name "unconnected-(U5A-IO_L5N_T0_AD9N_35-PadE19)") (class "Default")
      (node (ref "U5") (pin "E19") (pinfunction "IO_L5N_T0_AD9N_35_E19") (pintype "passive"))
    )
    (net (code "113") (name "unconnected-(U5A-IO_L5P_T0_34-PadT14)") (class "Default")
      (node (ref "U5") (pin "T14") (pinfunction "IO_L5P_T0_34_T14") (pintype "passive"))
    )
    (net (code "114") (name "unconnected-(U5A-IO_L5P_T0_AD9P_35-PadE18)") (class "Default")
      (node (ref "U5") (pin "E18") (pinfunction "IO_L5P_T0_AD9P_35_E18") (pintype "passive"))
    )
    (net (code "115") (name "unconnected-(U5A-IO_L6N_T0_VREF_34-PadR14)") (class "Default")
      (node (ref "U5") (pin "R14") (pinfunction "IO_L6N_T0_VREF_34_R14") (pintype "passive"))
    )
    (net (code "116") (name "unconnected-(U5A-IO_L6N_T0_VREF_35-PadF17)") (class "Default")
      (node (ref "U5") (pin "F17") (pinfunction "IO_L6N_T0_VREF_35_F17") (pintype "passive"))
    )
    (net (code "117") (name "unconnected-(U5A-IO_L6P_T0_34-PadP14)") (class "Default")
      (node (ref "U5") (pin "P14") (pinfunction "IO_L6P_T0_34_P14") (pintype "passive"))
    )
    (net (code "118") (name "unconnected-(U5A-IO_L6P_T0_35-PadF16)") (class "Default")
      (node (ref "U5") (pin "F16") (pinfunction "IO_L6P_T0_35_F16") (pintype "passive"))
    )
    (net (code "119") (name "unconnected-(U5A-IO_L7N_T1_34-PadY17)") (class "Default")
      (node (ref "U5") (pin "Y17") (pinfunction "IO_L7N_T1_34_Y17") (pintype "passive"))
    )
    (net (code "120") (name "unconnected-(U5A-IO_L7N_T1_AD2N_35-PadM20)") (class "Default")
      (node (ref "U5") (pin "M20") (pinfunction "IO_L7N_T1_AD2N_35_M20") (pintype "passive"))
    )
    (net (code "121") (name "unconnected-(U5A-IO_L7P_T1_34-PadY16)") (class "Default")
      (node (ref "U5") (pin "Y16") (pinfunction "IO_L7P_T1_34_Y16") (pintype "passive"))
    )
    (net (code "122") (name "unconnected-(U5A-IO_L7P_T1_AD2P_35-PadM19)") (class "Default")
      (node (ref "U5") (pin "M19") (pinfunction "IO_L7P_T1_AD2P_35_M19") (pintype "passive"))
    )
    (net (code "123") (name "unconnected-(U5A-IO_L8N_T1_34-PadY14)") (class "Default")
      (node (ref "U5") (pin "Y14") (pinfunction "IO_L8N_T1_34_Y14") (pintype "passive"))
    )
    (net (code "124") (name "unconnected-(U5A-IO_L8N_T1_AD10N_35-PadM18)") (class "Default")
      (node (ref "U5") (pin "M18") (pinfunction "IO_L8N_T1_AD10N_35_M18") (pintype "passive"))
    )
    (net (code "125") (name "unconnected-(U5A-IO_L8P_T1_34-PadW14)") (class "Default")
      (node (ref "U5") (pin "W14") (pinfunction "IO_L8P_T1_34_W14") (pintype "passive"))
    )
    (net (code "126") (name "unconnected-(U5A-IO_L8P_T1_AD10P_35-PadM17)") (class "Default")
      (node (ref "U5") (pin "M17") (pinfunction "IO_L8P_T1_AD10P_35_M17") (pintype "passive"))
    )
    (net (code "127") (name "unconnected-(U5A-IO_L9N_T1_DQS_34-PadU17)") (class "Default")
      (node (ref "U5") (pin "U17") (pinfunction "IO_L9N_T1_DQS_34_U17") (pintype "passive"))
    )
    (net (code "128") (name "unconnected-(U5A-IO_L9N_T1_DQS_AD3N_35-PadL20)") (class "Default")
      (node (ref "U5") (pin "L20") (pinfunction "IO_L9N_T1_DQS_AD3N_35_L20") (pintype "passive"))
    )
    (net (code "129") (name "unconnected-(U5A-IO_L9P_T1_DQS_34-PadT16)") (class "Default")
      (node (ref "U5") (pin "T16") (pinfunction "IO_L9P_T1_DQS_34_T16") (pintype "passive"))
    )
    (net (code "130") (name "unconnected-(U5A-IO_L9P_T1_DQS_AD3P_35-PadL19)") (class "Default")
      (node (ref "U5") (pin "L19") (pinfunction "IO_L9P_T1_DQS_AD3P_35_L19") (pintype "passive"))
    )
    (net (code "131") (name "unconnected-(U5A-IO_L10N_T1_34-PadW15)") (class "Default")
      (node (ref "U5") (pin "W15") (pinfunction "IO_L10N_T1_34_W15") (pintype "passive"))
    )
    (net (code "132") (name "unconnected-(U5A-IO_L10N_T1_AD11N_35-PadJ19)") (class "Default")
      (node (ref "U5") (pin "J19") (pinfunction "IO_L10N_T1_AD11N_35_J19") (pintype "passive"))
    )
    (net (code "133") (name "unconnected-(U5A-IO_L10P_T1_34-PadV15)") (class "Default")
      (node (ref "U5") (pin "V15") (pinfunction "IO_L10P_T1_34_V15") (pintype "passive"))
    )
    (net (code "134") (name "unconnected-(U5A-IO_L10P_T1_AD11P_35-PadK19)") (class "Default")
      (node (ref "U5") (pin "K19") (pinfunction "IO_L10P_T1_AD11P_35_K19") (pintype "passive"))
    )
    (net (code "135") (name "unconnected-(U5A-IO_L11N_T1_SRCC_34-PadU15)") (class "Default")
      (node (ref "U5") (pin "U15") (pinfunction "IO_L11N_T1_SRCC_34_U15") (pintype "passive"))
    )
    (net (code "136") (name "unconnected-(U5A-IO_L11N_T1_SRCC_35-PadL17)") (class "Default")
      (node (ref "U5") (pin "L17") (pinfunction "IO_L11N_T1_SRCC_35_L17") (pintype "passive"))
    )
    (net (code "137") (name "unconnected-(U5A-IO_L11P_T1_SRCC_34-PadU14)") (class "Default")
      (node (ref "U5") (pin "U14") (pinfunction "IO_L11P_T1_SRCC_34_U14") (pintype "passive"))
    )
    (net (code "138") (name "unconnected-(U5A-IO_L11P_T1_SRCC_35-PadL16)") (class "Default")
      (node (ref "U5") (pin "L16") (pinfunction "IO_L11P_T1_SRCC_35_L16") (pintype "passive"))
    )
    (net (code "139") (name "unconnected-(U5A-IO_L12N_T1_MRCC_34-PadU19)") (class "Default")
      (node (ref "U5") (pin "U19") (pinfunction "IO_L12N_T1_MRCC_34_U19") (pintype "passive"))
    )
    (net (code "140") (name "unconnected-(U5A-IO_L12N_T1_MRCC_35-PadK18)") (class "Default")
      (node (ref "U5") (pin "K18") (pinfunction "IO_L12N_T1_MRCC_35_K18") (pintype "passive"))
    )
    (net (code "141") (name "unconnected-(U5A-IO_L12P_T1_MRCC_34-PadU18)") (class "Default")
      (node (ref "U5") (pin "U18") (pinfunction "IO_L12P_T1_MRCC_34_U18") (pintype "passive"))
    )
    (net (code "142") (name "unconnected-(U5A-IO_L12P_T1_MRCC_35-PadK17)") (class "Default")
      (node (ref "U5") (pin "K17") (pinfunction "IO_L12P_T1_MRCC_35_K17") (pintype "passive"))
    )
    (net (code "143") (name "unconnected-(U5A-IO_L13N_T2_MRCC_35-PadH17)") (class "Default")
      (node (ref "U5") (pin "H17") (pinfunction "IO_L13N_T2_MRCC_35_H17") (pintype "passive"))
    )
    (net (code "144") (name "unconnected-(U5A-IO_L13P_T2_MRCC_35-PadH16)") (class "Default")
      (node (ref "U5") (pin "H16") (pinfunction "IO_L13P_T2_MRCC_35_H16") (pintype "passive"))
    )
    (net (code "145") (name "unconnected-(U5A-IO_L14N_T2_AD4N_SRCC_35-PadH18)") (class "Default")
      (node (ref "U5") (pin "H18") (pinfunction "IO_L14N_T2_AD4N_SRCC_35_H18") (pintype "passive"))
    )
    (net (code "146") (name "unconnected-(U5A-IO_L14N_T2_SRCC_34-PadP20)") (class "Default")
      (node (ref "U5") (pin "P20") (pinfunction "IO_L14N_T2_SRCC_34_P20") (pintype "passive"))
    )
    (net (code "147") (name "unconnected-(U5A-IO_L14P_T2_AD4P_SRCC_35-PadJ18)") (class "Default")
      (node (ref "U5") (pin "J18") (pinfunction "IO_L14P_T2_AD4P_SRCC_35_J18") (pintype "passive"))
    )
    (net (code "148") (name "unconnected-(U5A-IO_L14P_T2_SRCC_34-PadN20)") (class "Default")
      (node (ref "U5") (pin "N20") (pinfunction "IO_L14P_T2_SRCC_34_N20") (pintype "passive"))
    )
    (net (code "149") (name "unconnected-(U5A-IO_L15N_T2_DQS_34-PadU20)") (class "Default")
      (node (ref "U5") (pin "U20") (pinfunction "IO_L15N_T2_DQS_34_U20") (pintype "passive"))
    )
    (net (code "150") (name "unconnected-(U5A-IO_L15N_T2_DQS_AD12N_35-PadF20)") (class "Default")
      (node (ref "U5") (pin "F20") (pinfunction "IO_L15N_T2_DQS_AD12N_35_F20") (pintype "passive"))
    )
    (net (code "151") (name "unconnected-(U5A-IO_L15P_T2_DQS_34-PadT20)") (class "Default")
      (node (ref "U5") (pin "T20") (pinfunction "IO_L15P_T2_DQS_34_T20") (pintype "passive"))
    )
    (net (code "152") (name "unconnected-(U5A-IO_L15P_T2_DQS_AD12P_35-PadF19)") (class "Default")
      (node (ref "U5") (pin "F19") (pinfunction "IO_L15P_T2_DQS_AD12P_35_F19") (pintype "passive"))
    )
    (net (code "153") (name "unconnected-(U5A-IO_L16N_T2_34-PadW20)") (class "Default")
      (node (ref "U5") (pin "W20") (pinfunction "IO_L16N_T2_34_W20") (pintype "passive"))
    )
    (net (code "154") (name "unconnected-(U5A-IO_L16N_T2_35-PadG18)") (class "Default")
      (node (ref "U5") (pin "G18") (pinfunction "IO_L16N_T2_35_G18") (pintype "passive"))
    )
    (net (code "155") (name "unconnected-(U5A-IO_L16P_T2_34-PadV20)") (class "Default")
      (node (ref "U5") (pin "V20") (pinfunction "IO_L16P_T2_34_V20") (pintype "passive"))
    )
    (net (code "156") (name "unconnected-(U5A-IO_L16P_T2_35-PadG17)") (class "Default")
      (node (ref "U5") (pin "G17") (pinfunction "IO_L16P_T2_35_G17") (pintype "passive"))
    )
    (net (code "157") (name "unconnected-(U5A-IO_L17N_T2_34-PadY19)") (class "Default")
      (node (ref "U5") (pin "Y19") (pinfunction "IO_L17N_T2_34_Y19") (pintype "passive"))
    )
    (net (code "158") (name "unconnected-(U5A-IO_L17N_T2_AD5N_35-PadH20)") (class "Default")
      (node (ref "U5") (pin "H20") (pinfunction "IO_L17N_T2_AD5N_35_H20") (pintype "passive"))
    )
    (net (code "159") (name "unconnected-(U5A-IO_L17P_T2_34-PadY18)") (class "Default")
      (node (ref "U5") (pin "Y18") (pinfunction "IO_L17P_T2_34_Y18") (pintype "passive"))
    )
    (net (code "160") (name "unconnected-(U5A-IO_L17P_T2_AD5P_35-PadJ20)") (class "Default")
      (node (ref "U5") (pin "J20") (pinfunction "IO_L17P_T2_AD5P_35_J20") (pintype "passive"))
    )
    (net (code "161") (name "unconnected-(U5A-IO_L18N_T2_34-PadW16)") (class "Default")
      (node (ref "U5") (pin "W16") (pinfunction "IO_L18N_T2_34_W16") (pintype "passive"))
    )
    (net (code "162") (name "unconnected-(U5A-IO_L18N_T2_AD13N_35-PadG20)") (class "Default")
      (node (ref "U5") (pin "G20") (pinfunction "IO_L18N_T2_AD13N_35_G20") (pintype "passive"))
    )
    (net (code "163") (name "unconnected-(U5A-IO_L18P_T2_34-PadV16)") (class "Default")
      (node (ref "U5") (pin "V16") (pinfunction "IO_L18P_T2_34_V16") (pintype "passive"))
    )
    (net (code "164") (name "unconnected-(U5A-IO_L18P_T2_AD13P_35-PadG19)") (class "Default")
      (node (ref "U5") (pin "G19") (pinfunction "IO_L18P_T2_AD13P_35_G19") (pintype "passive"))
    )
    (net (code "165") (name "unconnected-(U5A-IO_L19N_T3_VREF_34-PadR17)") (class "Default")
      (node (ref "U5") (pin "R17") (pinfunction "IO_L19N_T3_VREF_34_R17") (pintype "passive"))
    )
    (net (code "166") (name "unconnected-(U5A-IO_L19N_T3_VREF_35-PadG15)") (class "Default")
      (node (ref "U5") (pin "G15") (pinfunction "IO_L19N_T3_VREF_35_G15") (pintype "passive"))
    )
    (net (code "167") (name "unconnected-(U5A-IO_L19P_T3_34-PadR16)") (class "Default")
      (node (ref "U5") (pin "R16") (pinfunction "IO_L19P_T3_34_R16") (pintype "passive"))
    )
    (net (code "168") (name "unconnected-(U5A-IO_L19P_T3_35-PadH15)") (class "Default")
      (node (ref "U5") (pin "H15") (pinfunction "IO_L19P_T3_35_H15") (pintype "passive"))
    )
    (net (code "169") (name "unconnected-(U5A-IO_L20N_T3_34-PadR18)") (class "Default")
      (node (ref "U5") (pin "R18") (pinfunction "IO_L20N_T3_34_R18") (pintype "passive"))
    )
    (net (code "170") (name "unconnected-(U5A-IO_L20N_T3_AD6N_35-PadJ14)") (class "Default")
      (node (ref "U5") (pin "J14") (pinfunction "IO_L20N_T3_AD6N_35_J14") (pintype "passive"))
    )
    (net (code "171") (name "unconnected-(U5A-IO_L20P_T3_34-PadT17)") (class "Default")
      (node (ref "U5") (pin "T17") (pinfunction "IO_L20P_T3_34_T17") (pintype "passive"))
    )
    (net (code "172") (name "unconnected-(U5A-IO_L20P_T3_AD6P_35-PadK14)") (class "Default")
      (node (ref "U5") (pin "K14") (pinfunction "IO_L20P_T3_AD6P_35_K14") (pintype "passive"))
    )
    (net (code "173") (name "unconnected-(U5A-IO_L21N_T3_DQS_34-PadV18)") (class "Default")
      (node (ref "U5") (pin "V18") (pinfunction "IO_L21N_T3_DQS_34_V18") (pintype "passive"))
    )
    (net (code "174") (name "unconnected-(U5A-IO_L21N_T3_DQS_AD14N_35-PadN16)") (class "Default")
      (node (ref "U5") (pin "N16") (pinfunction "IO_L21N_T3_DQS_AD14N_35_N16") (pintype "passive"))
    )
    (net (code "175") (name "unconnected-(U5A-IO_L21P_T3_DQS_34-PadV17)") (class "Default")
      (node (ref "U5") (pin "V17") (pinfunction "IO_L21P_T3_DQS_34_V17") (pintype "passive"))
    )
    (net (code "176") (name "unconnected-(U5A-IO_L21P_T3_DQS_AD14P_35-PadN15)") (class "Default")
      (node (ref "U5") (pin "N15") (pinfunction "IO_L21P_T3_DQS_AD14P_35_N15") (pintype "passive"))
    )
    (net (code "177") (name "unconnected-(U5A-IO_L22N_T3_34-PadW19)") (class "Default")
      (node (ref "U5") (pin "W19") (pinfunction "IO_L22N_T3_34_W19") (pintype "passive"))
    )
    (net (code "178") (name "unconnected-(U5A-IO_L22N_T3_AD7N_35-PadL15)") (class "Default")
      (node (ref "U5") (pin "L15") (pinfunction "IO_L22N_T3_AD7N_35_L15") (pintype "passive"))
    )
    (net (code "179") (name "unconnected-(U5A-IO_L22P_T3_34-PadW18)") (class "Default")
      (node (ref "U5") (pin "W18") (pinfunction "IO_L22P_T3_34_W18") (pintype "passive"))
    )
    (net (code "180") (name "unconnected-(U5A-IO_L22P_T3_AD7P_35-PadL14)") (class "Default")
      (node (ref "U5") (pin "L14") (pinfunction "IO_L22P_T3_AD7P_35_L14") (pintype "passive"))
    )
    (net (code "181") (name "unconnected-(U5A-IO_L23N_T3_34-PadP18)") (class "Default")
      (node (ref "U5") (pin "P18") (pinfunction "IO_L23N_T3_34_P18") (pintype "passive"))
    )
    (net (code "182") (name "unconnected-(U5A-IO_L23N_T3_35-PadM15)") (class "Default")
      (node (ref "U5") (pin "M15") (pinfunction "IO_L23N_T3_35_M15") (pintype "passive"))
    )
    (net (code "183") (name "unconnected-(U5A-IO_L23P_T3_34-PadN17)") (class "Default")
      (node (ref "U5") (pin "N17") (pinfunction "IO_L23P_T3_34_N17") (pintype "passive"))
    )
    (net (code "184") (name "unconnected-(U5A-IO_L23P_T3_35-PadM14)") (class "Default")
      (node (ref "U5") (pin "M14") (pinfunction "IO_L23P_T3_35_M14") (pintype "passive"))
    )
    (net (code "185") (name "unconnected-(U5A-IO_L24N_T3_34-PadP16)") (class "Default")
      (node (ref "U5") (pin "P16") (pinfunction "IO_L24N_T3_34_P16") (pintype "passive"))
    )
    (net (code "186") (name "unconnected-(U5A-IO_L24N_T3_AD15N_35-PadJ16)") (class "Default")
      (node (ref "U5") (pin "J16") (pinfunction "IO_L24N_T3_AD15N_35_J16") (pintype "passive"))
    )
    (net (code "187") (name "unconnected-(U5A-IO_L24P_T3_34-PadP15)") (class "Default")
      (node (ref "U5") (pin "P15") (pinfunction "IO_L24P_T3_34_P15") (pintype "passive"))
    )
    (net (code "188") (name "unconnected-(U5A-IO_L24P_T3_AD15P_35-PadK16)") (class "Default")
      (node (ref "U5") (pin "K16") (pinfunction "IO_L24P_T3_AD15P_35_K16") (pintype "passive"))
    )
    (net (code "189") (name "unconnected-(U5B-IO_L6N_T0_VREF_13-PadV5)") (class "Default")
      (node (ref "U5") (pin "V5") (pinfunction "IO_L6N_T0_VREF_13_V5") (pintype "passive"))
    )
    (net (code "190") (name "unconnected-(U5B-IO_L11N_T1_SRCC_13-PadV7)") (class "Default")
      (node (ref "U5") (pin "V7") (pinfunction "IO_L11N_T1_SRCC_13_V7") (pintype "passive"))
    )
    (net (code "191") (name "unconnected-(U5B-IO_L11P_T1_SRCC_13-PadU7)") (class "Default")
      (node (ref "U5") (pin "U7") (pinfunction "IO_L11P_T1_SRCC_13_U7") (pintype "passive"))
    )
    (net (code "192") (name "unconnected-(U5B-IO_L12N_T1_MRCC_13-PadU10)") (class "Default")
      (node (ref "U5") (pin "U10") (pinfunction "IO_L12N_T1_MRCC_13_U10") (pintype "passive"))
    )
    (net (code "193") (name "unconnected-(U5B-IO_L12P_T1_MRCC_13-PadT9)") (class "Default")
      (node (ref "U5") (pin "T9") (pinfunction "IO_L12P_T1_MRCC_13_T9") (pintype "passive"))
    )
    (net (code "194") (name "unconnected-(U5B-IO_L13N_T2_MRCC_13-PadY6)") (class "Default")
      (node (ref "U5") (pin "Y6") (pinfunction "IO_L13N_T2_MRCC_13_Y6") (pintype "passive"))
    )
    (net (code "195") (name "unconnected-(U5B-IO_L13P_T2_MRCC_13-PadY7)") (class "Default")
      (node (ref "U5") (pin "Y7") (pinfunction "IO_L13P_T2_MRCC_13_Y7") (pintype "passive"))
    )
    (net (code "196") (name "unconnected-(U5B-IO_L14N_T2_SRCC_13-PadY8)") (class "Default")
      (node (ref "U5") (pin "Y8") (pinfunction "IO_L14N_T2_SRCC_13_Y8") (pintype "passive"))
    )
    (net (code "197") (name "unconnected-(U5B-IO_L14P_T2_SRCC_13-PadY9)") (class "Default")
      (node (ref "U5") (pin "Y9") (pinfunction "IO_L14P_T2_SRCC_13_Y9") (pintype "passive"))
    )
    (net (code "198") (name "unconnected-(U5B-IO_L15N_T2_DQS_13-PadW8)") (class "Default")
      (node (ref "U5") (pin "W8") (pinfunction "IO_L15N_T2_DQS_13_W8") (pintype "passive"))
    )
    (net (code "199") (name "unconnected-(U5B-IO_L15P_T2_DQS_13-PadV8)") (class "Default")
      (node (ref "U5") (pin "V8") (pinfunction "IO_L15P_T2_DQS_13_V8") (pintype "passive"))
    )
    (net (code "200") (name "unconnected-(U5B-IO_L16N_T2_13-PadW9)") (class "Default")
      (node (ref "U5") (pin "W9") (pinfunction "IO_L16N_T2_13_W9") (pintype "passive"))
    )
    (net (code "201") (name "unconnected-(U5B-IO_L16P_T2_13-PadW10)") (class "Default")
      (node (ref "U5") (pin "W10") (pinfunction "IO_L16P_T2_13_W10") (pintype "passive"))
    )
    (net (code "202") (name "unconnected-(U5B-IO_L17N_T2_13-PadU8)") (class "Default")
      (node (ref "U5") (pin "U8") (pinfunction "IO_L17N_T2_13_U8") (pintype "passive"))
    )
    (net (code "203") (name "unconnected-(U5B-IO_L17P_T2_13-PadU9)") (class "Default")
      (node (ref "U5") (pin "U9") (pinfunction "IO_L17P_T2_13_U9") (pintype "passive"))
    )
    (net (code "204") (name "unconnected-(U5B-IO_L18N_T2_13-PadY11)") (class "Default")
      (node (ref "U5") (pin "Y11") (pinfunction "IO_L18N_T2_13_Y11") (pintype "passive"))
    )
    (net (code "205") (name "unconnected-(U5B-IO_L18P_T2_13-PadW11)") (class "Default")
      (node (ref "U5") (pin "W11") (pinfunction "IO_L18P_T2_13_W11") (pintype "passive"))
    )
    (net (code "206") (name "unconnected-(U5B-IO_L19N_T3_VREF_13-PadU5)") (class "Default")
      (node (ref "U5") (pin "U5") (pinfunction "IO_L19N_T3_VREF_13_U5") (pintype "passive"))
    )
    (net (code "207") (name "unconnected-(U5B-IO_L19P_T3_13-PadT5)") (class "Default")
      (node (ref "U5") (pin "T5") (pinfunction "IO_L19P_T3_13_T5") (pintype "passive"))
    )
    (net (code "208") (name "unconnected-(U5B-IO_L20N_T3_13-PadY13)") (class "Default")
      (node (ref "U5") (pin "Y13") (pinfunction "IO_L20N_T3_13_Y13") (pintype "passive"))
    )
    (net (code "209") (name "unconnected-(U5B-IO_L20P_T3_13-PadY12)") (class "Default")
      (node (ref "U5") (pin "Y12") (pinfunction "IO_L20P_T3_13_Y12") (pintype "passive"))
    )
    (net (code "210") (name "unconnected-(U5B-IO_L21N_T3_DQS_13-PadV10)") (class "Default")
      (node (ref "U5") (pin "V10") (pinfunction "IO_L21N_T3_DQS_13_V10") (pintype "passive"))
    )
    (net (code "211") (name "unconnected-(U5B-IO_L21P_T3_DQS_13-PadV11)") (class "Default")
      (node (ref "U5") (pin "V11") (pinfunction "IO_L21P_T3_DQS_13_V11") (pintype "passive"))
    )
    (net (code "212") (name "unconnected-(U5B-IO_L22N_T3_13-PadW6)") (class "Default")
      (node (ref "U5") (pin "W6") (pinfunction "IO_L22N_T3_13_W6") (pintype "passive"))
    )
    (net (code "213") (name "unconnected-(U5B-IO_L22P_T3_13-PadV6)") (class "Default")
      (node (ref "U5") (pin "V6") (pinfunction "IO_L22P_T3_13_V6") (pintype "passive"))
    )
    (net (code "214") (name "unconnected-(U5B-PS_MIO0_500-PadE6)") (class "Default")
      (node (ref "U5") (pin "E6") (pinfunction "PS_MIO0_500_E6") (pintype "passive"))
    )
    (net (code "215") (name "unconnected-(U5B-PS_MIO7_500-PadD8)") (class "Default")
      (node (ref "U5") (pin "D8") (pinfunction "PS_MIO7_500_D8") (pintype "passive"))
    )
    (net (code "216") (name "unconnected-(U5B-PS_MIO8_500-PadD5)") (class "Default")
      (node (ref "U5") (pin "D5") (pinfunction "PS_MIO8_500_D5") (pintype "passive"))
    )
    (net (code "217") (name "unconnected-(U5B-PS_MIO9_500-PadB5)") (class "Default")
      (node (ref "U5") (pin "B5") (pinfunction "PS_MIO9_500_B5") (pintype "passive"))
    )
    (net (code "218") (name "unconnected-(U5B-PS_MIO10_500-PadE9)") (class "Default")
      (node (ref "U5") (pin "E9") (pinfunction "PS_MIO10_500_E9") (pintype "passive"))
    )
    (net (code "219") (name "unconnected-(U5B-PS_MIO11_500-PadC6)") (class "Default")
      (node (ref "U5") (pin "C6") (pinfunction "PS_MIO11_500_C6") (pintype "passive"))
    )
    (net (code "220") (name "unconnected-(U5B-PS_MIO16_501-PadA19)") (class "Default")
      (node (ref "U5") (pin "A19") (pinfunction "PS_MIO16_501_A19") (pintype "passive"))
    )
    (net (code "221") (name "unconnected-(U5B-PS_MIO17_501-PadE14)") (class "Default")
      (node (ref "U5") (pin "E14") (pinfunction "PS_MIO17_501_E14") (pintype "passive"))
    )
    (net (code "222") (name "unconnected-(U5B-PS_MIO18_501-PadB18)") (class "Default")
      (node (ref "U5") (pin "B18") (pinfunction "PS_MIO18_501_B18") (pintype "passive"))
    )
    (net (code "223") (name "unconnected-(U5B-PS_MIO19_501-PadD10)") (class "Default")
      (node (ref "U5") (pin "D10") (pinfunction "PS_MIO19_501_D10") (pintype "passive"))
    )
    (net (code "224") (name "unconnected-(U5B-PS_MIO20_501-PadA17)") (class "Default")
      (node (ref "U5") (pin "A17") (pinfunction "PS_MIO20_501_A17") (pintype "passive"))
    )
    (net (code "225") (name "unconnected-(U5B-PS_MIO21_501-PadF14)") (class "Default")
      (node (ref "U5") (pin "F14") (pinfunction "PS_MIO21_501_F14") (pintype "passive"))
    )
    (net (code "226") (name "unconnected-(U5B-PS_MIO22_501-PadB17)") (class "Default")
      (node (ref "U5") (pin "B17") (pinfunction "PS_MIO22_501_B17") (pintype "passive"))
    )
    (net (code "227") (name "unconnected-(U5B-PS_MIO23_501-PadD11)") (class "Default")
      (node (ref "U5") (pin "D11") (pinfunction "PS_MIO23_501_D11") (pintype "passive"))
    )
    (net (code "228") (name "unconnected-(U5B-PS_MIO24_501-PadA16)") (class "Default")
      (node (ref "U5") (pin "A16") (pinfunction "PS_MIO24_501_A16") (pintype "passive"))
    )
    (net (code "229") (name "unconnected-(U5B-PS_MIO25_501-PadF15)") (class "Default")
      (node (ref "U5") (pin "F15") (pinfunction "PS_MIO25_501_F15") (pintype "passive"))
    )
    (net (code "230") (name "unconnected-(U5B-PS_MIO26_501-PadA15)") (class "Default")
      (node (ref "U5") (pin "A15") (pinfunction "PS_MIO26_501_A15") (pintype "passive"))
    )
    (net (code "231") (name "unconnected-(U5B-PS_MIO27_501-PadD13)") (class "Default")
      (node (ref "U5") (pin "D13") (pinfunction "PS_MIO27_501_D13") (pintype "passive"))
    )
    (net (code "232") (name "unconnected-(U5B-PS_MIO28_501-PadC16)") (class "Default")
      (node (ref "U5") (pin "C16") (pinfunction "PS_MIO28_501_C16") (pintype "passive"))
    )
    (net (code "233") (name "unconnected-(U5B-PS_MIO29_501-PadC13)") (class "Default")
      (node (ref "U5") (pin "C13") (pinfunction "PS_MIO29_501_C13") (pintype "passive"))
    )
    (net (code "234") (name "unconnected-(U5B-PS_MIO30_501-PadC15)") (class "Default")
      (node (ref "U5") (pin "C15") (pinfunction "PS_MIO30_501_C15") (pintype "passive"))
    )
    (net (code "235") (name "unconnected-(U5B-PS_MIO31_501-PadE16)") (class "Default")
      (node (ref "U5") (pin "E16") (pinfunction "PS_MIO31_501_E16") (pintype "passive"))
    )
    (net (code "236") (name "unconnected-(U5B-PS_MIO32_501-PadA14)") (class "Default")
      (node (ref "U5") (pin "A14") (pinfunction "PS_MIO32_501_A14") (pintype "passive"))
    )
    (net (code "237") (name "unconnected-(U5B-PS_MIO33_501-PadD15)") (class "Default")
      (node (ref "U5") (pin "D15") (pinfunction "PS_MIO33_501_D15") (pintype "passive"))
    )
    (net (code "238") (name "unconnected-(U5B-PS_MIO34_501-PadA12)") (class "Default")
      (node (ref "U5") (pin "A12") (pinfunction "PS_MIO34_501_A12") (pintype "passive"))
    )
    (net (code "239") (name "unconnected-(U5B-PS_MIO35_501-PadF12)") (class "Default")
      (node (ref "U5") (pin "F12") (pinfunction "PS_MIO35_501_F12") (pintype "passive"))
    )
    (net (code "240") (name "unconnected-(U5B-PS_MIO36_501-PadA11)") (class "Default")
      (node (ref "U5") (pin "A11") (pinfunction "PS_MIO36_501_A11") (pintype "passive"))
    )
    (net (code "241") (name "unconnected-(U5B-PS_MIO37_501-PadA10)") (class "Default")
      (node (ref "U5") (pin "A10") (pinfunction "PS_MIO37_501_A10") (pintype "passive"))
    )
    (net (code "242") (name "unconnected-(U5B-PS_MIO38_501-PadE13)") (class "Default")
      (node (ref "U5") (pin "E13") (pinfunction "PS_MIO38_501_E13") (pintype "passive"))
    )
    (net (code "243") (name "unconnected-(U5B-PS_MIO39_501-PadC18)") (class "Default")
      (node (ref "U5") (pin "C18") (pinfunction "PS_MIO39_501_C18") (pintype "passive"))
    )
    (net (code "244") (name "unconnected-(U5B-PS_MIO40_501-PadD14)") (class "Default")
      (node (ref "U5") (pin "D14") (pinfunction "PS_MIO40_501_D14") (pintype "passive"))
    )
    (net (code "245") (name "unconnected-(U5B-PS_MIO41_501-PadC17)") (class "Default")
      (node (ref "U5") (pin "C17") (pinfunction "PS_MIO41_501_C17") (pintype "passive"))
    )
    (net (code "246") (name "unconnected-(U5B-PS_MIO42_501-PadE12)") (class "Default")
      (node (ref "U5") (pin "E12") (pinfunction "PS_MIO42_501_E12") (pintype "passive"))
    )
    (net (code "247") (name "unconnected-(U5B-PS_MIO43_501-PadA9)") (class "Default")
      (node (ref "U5") (pin "A9") (pinfunction "PS_MIO43_501_A9") (pintype "passive"))
    )
    (net (code "248") (name "unconnected-(U5B-PS_MIO44_501-PadF13)") (class "Default")
      (node (ref "U5") (pin "F13") (pinfunction "PS_MIO44_501_F13") (pintype "passive"))
    )
    (net (code "249") (name "unconnected-(U5B-PS_MIO45_501-PadB15)") (class "Default")
      (node (ref "U5") (pin "B15") (pinfunction "PS_MIO45_501_B15") (pintype "passive"))
    )
    (net (code "250") (name "unconnected-(U5B-PS_MIO46_501-PadD16)") (class "Default")
      (node (ref "U5") (pin "D16") (pinfunction "PS_MIO46_501_D16") (pintype "passive"))
    )
    (net (code "251") (name "unconnected-(U5B-PS_MIO47_501-PadB14)") (class "Default")
      (node (ref "U5") (pin "B14") (pinfunction "PS_MIO47_501_B14") (pintype "passive"))
    )
    (net (code "252") (name "unconnected-(U5B-PS_MIO48_501-PadB12)") (class "Default")
      (node (ref "U5") (pin "B12") (pinfunction "PS_MIO48_501_B12") (pintype "passive"))
    )
    (net (code "253") (name "unconnected-(U5B-PS_MIO49_501-PadC12)") (class "Default")
      (node (ref "U5") (pin "C12") (pinfunction "PS_MIO49_501_C12") (pintype "passive"))
    )
    (net (code "254") (name "unconnected-(U5B-PS_MIO50_501-PadB13)") (class "Default")
      (node (ref "U5") (pin "B13") (pinfunction "PS_MIO50_501_B13") (pintype "passive"))
    )
    (net (code "255") (name "unconnected-(U5B-PS_MIO51_501-PadB9)") (class "Default")
      (node (ref "U5") (pin "B9") (pinfunction "PS_MIO51_501_B9") (pintype "passive"))
    )
    (net (code "256") (name "unconnected-(U5B-PS_MIO52_501-PadC10)") (class "Default")
      (node (ref "U5") (pin "C10") (pinfunction "PS_MIO52_501_C10") (pintype "passive"))
    )
    (net (code "257") (name "unconnected-(U5B-PS_MIO53_501-PadC11)") (class "Default")
      (node (ref "U5") (pin "C11") (pinfunction "PS_MIO53_501_C11") (pintype "passive"))
    )
    (net (code "258") (name "unconnected-(U5B-VN_0-PadL10)") (class "Default")
      (node (ref "U5") (pin "L10") (pinfunction "VN_0_L10") (pintype "passive"))
    )
    (net (code "259") (name "unconnected-(U5B-VP_0-PadK9)") (class "Default")
      (node (ref "U5") (pin "K9") (pinfunction "VP_0_K9") (pintype "passive"))
    )
    (net (code "260") (name "unconnected-(U7A-NC-PadJ1)") (class "Default")
      (node (ref "U7") (pin "J1") (pinfunction "NC_J1") (pintype "passive"))
    )
    (net (code "261") (name "unconnected-(U7A-NC-PadJ9)") (class "Default")
      (node (ref "U7") (pin "J9") (pinfunction "NC_J9") (pintype "passive"))
    )
    (net (code "262") (name "unconnected-(U7A-NC-PadL1)") (class "Default")
      (node (ref "U7") (pin "L1") (pinfunction "NC_L1") (pintype "passive"))
    )
    (net (code "263") (name "unconnected-(U7A-NC-PadL9)") (class "Default")
      (node (ref "U7") (pin "L9") (pinfunction "NC_L9") (pintype "passive"))
    )
    (net (code "264") (name "unconnected-(U7A-NC-PadM7)") (class "Default")
      (node (ref "U7") (pin "M7") (pinfunction "NC_M7") (pintype "passive"))
    )
  )
)
